# CAN_Mirror.net
KiCad netlist of a schematic drawn in EAGLE
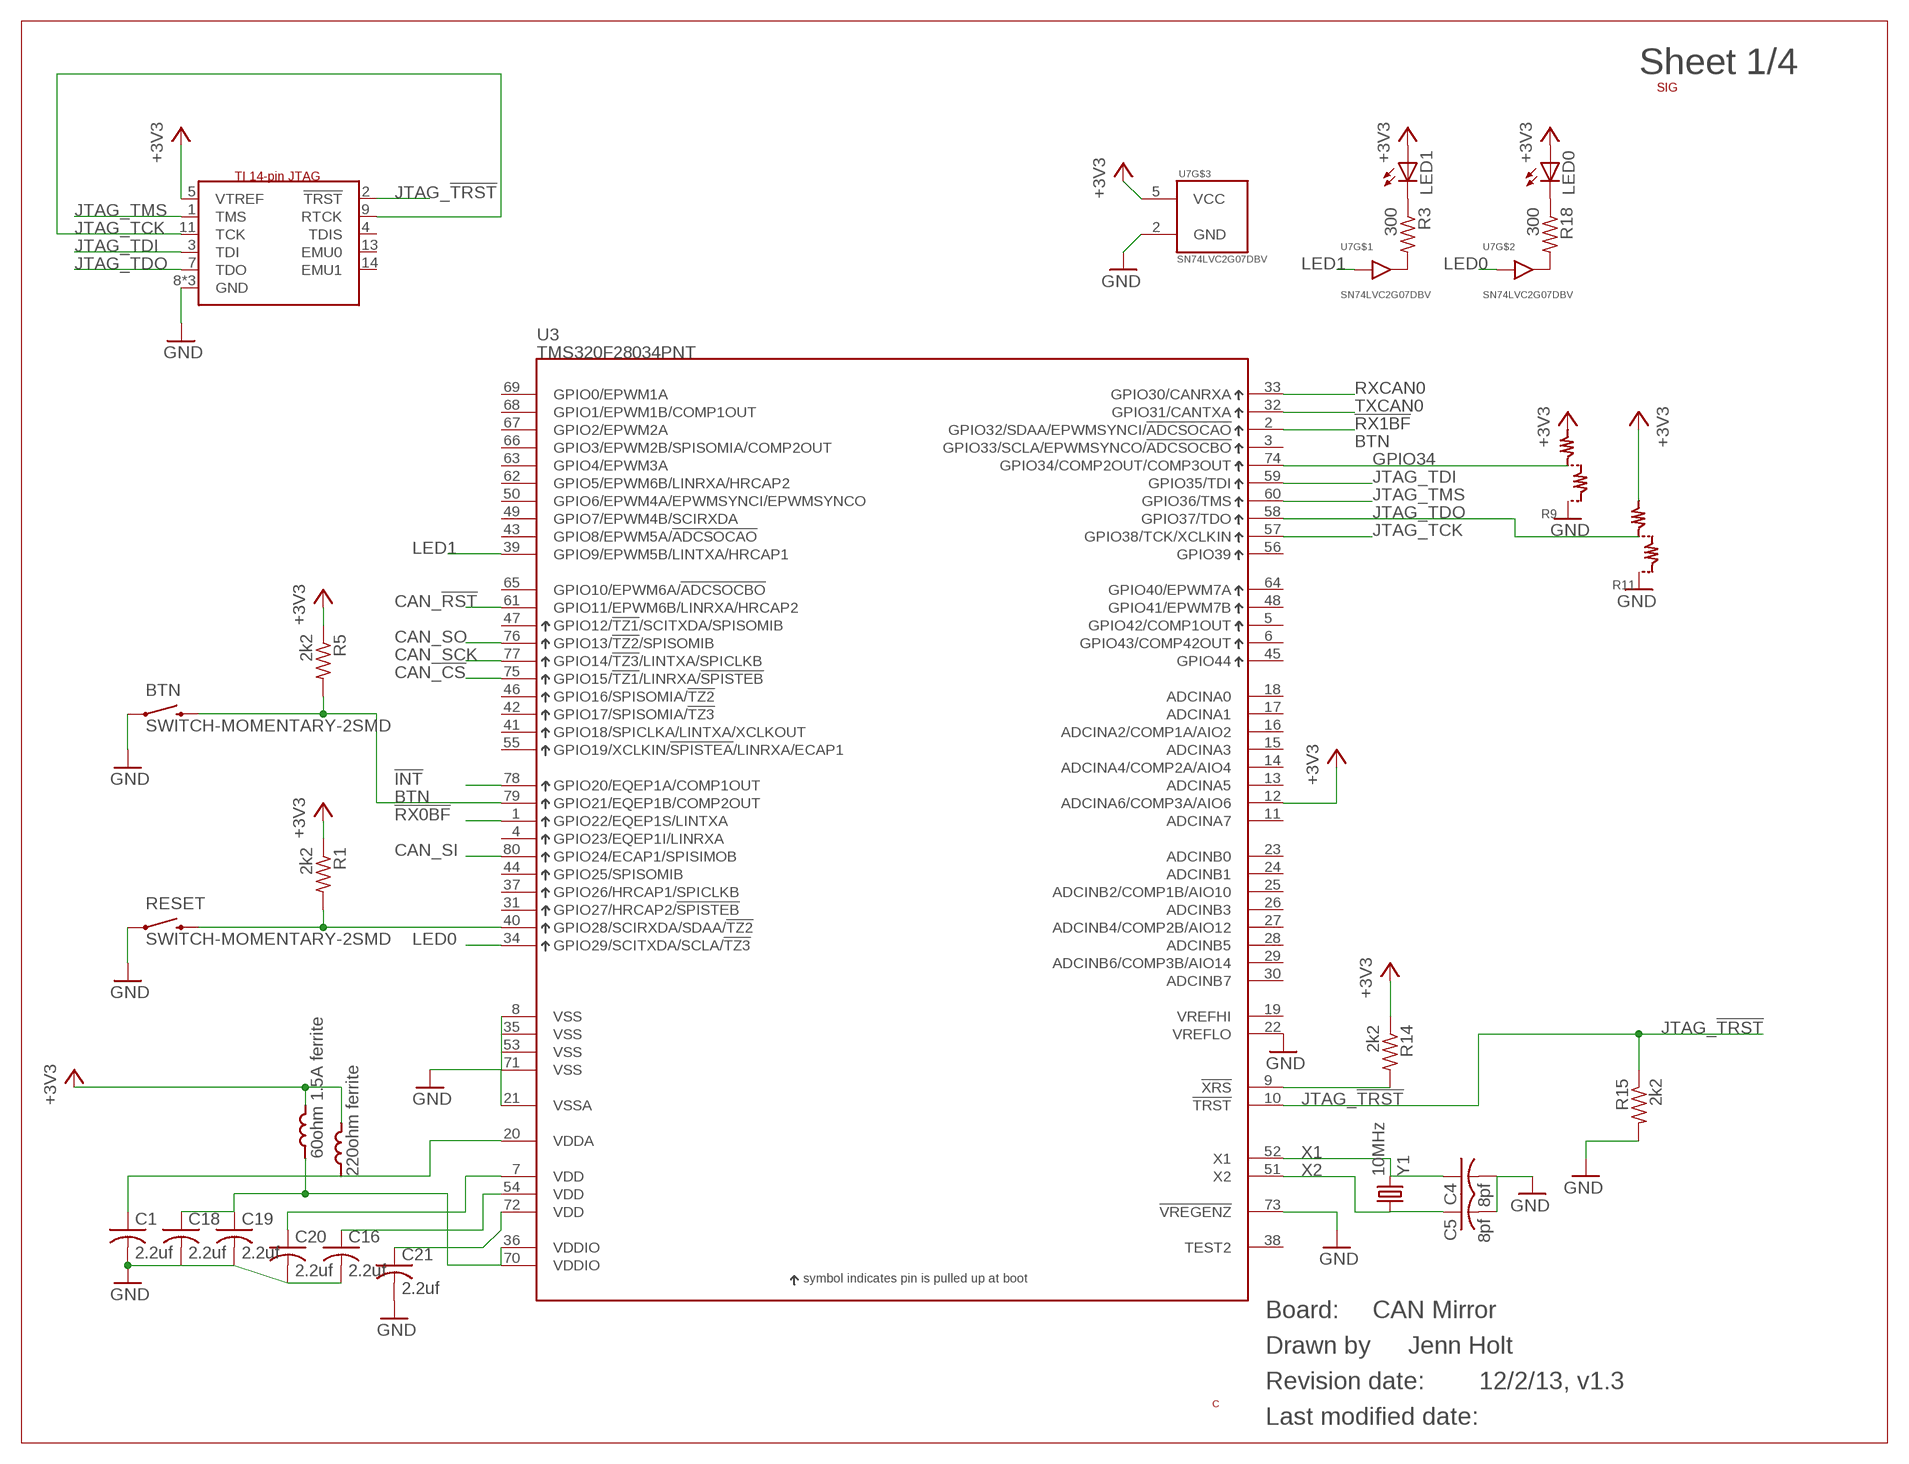
[diagram p0: schematic, sheet 1]
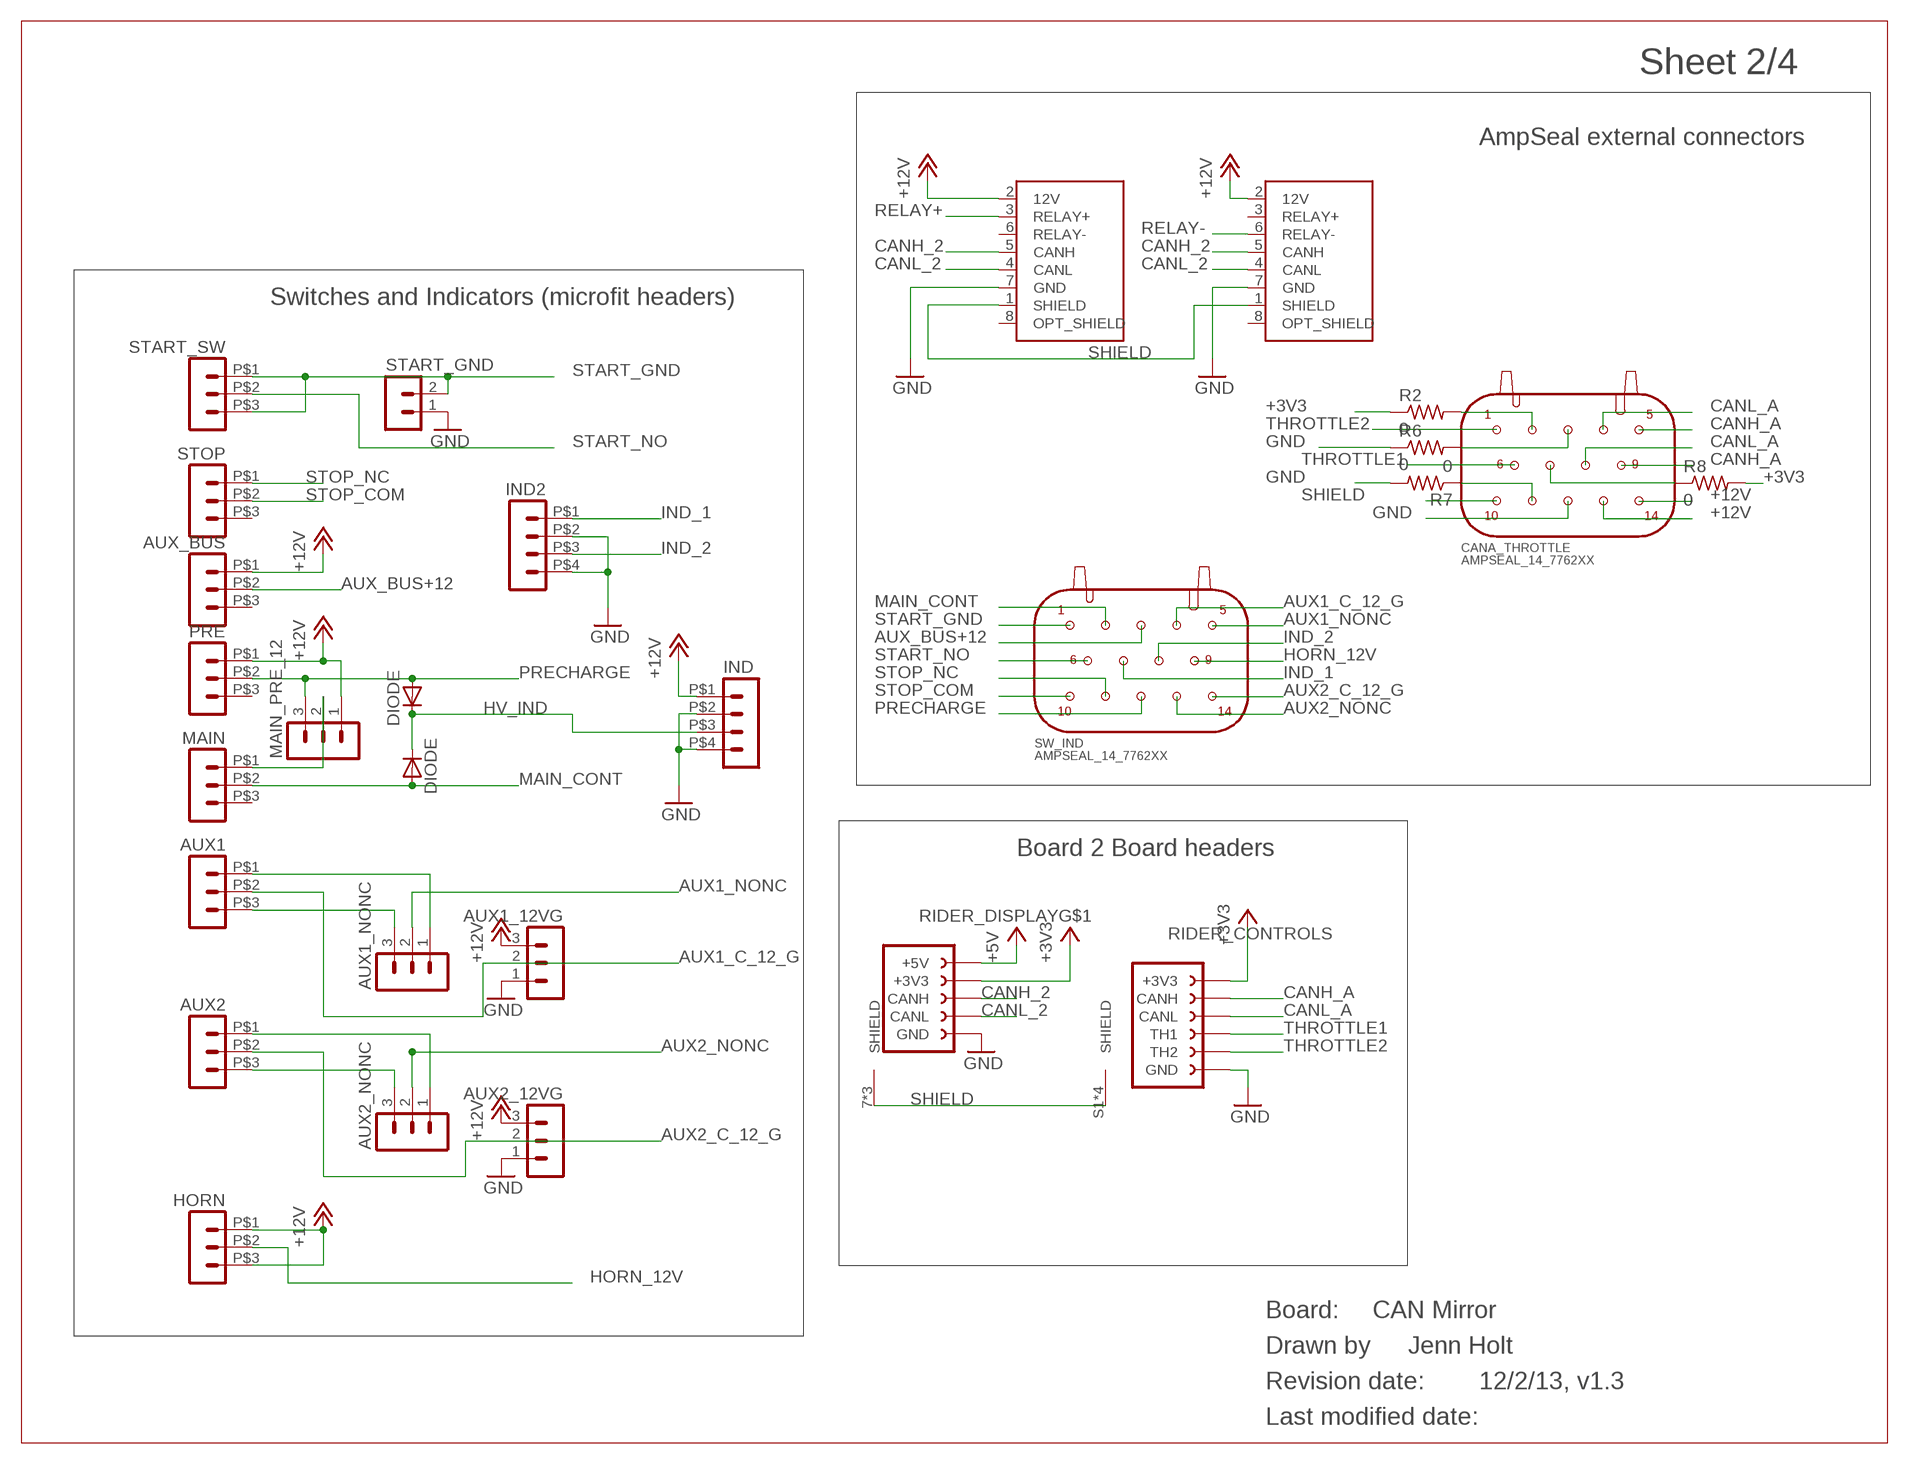
[diagram p1: schematic, sheet 2]
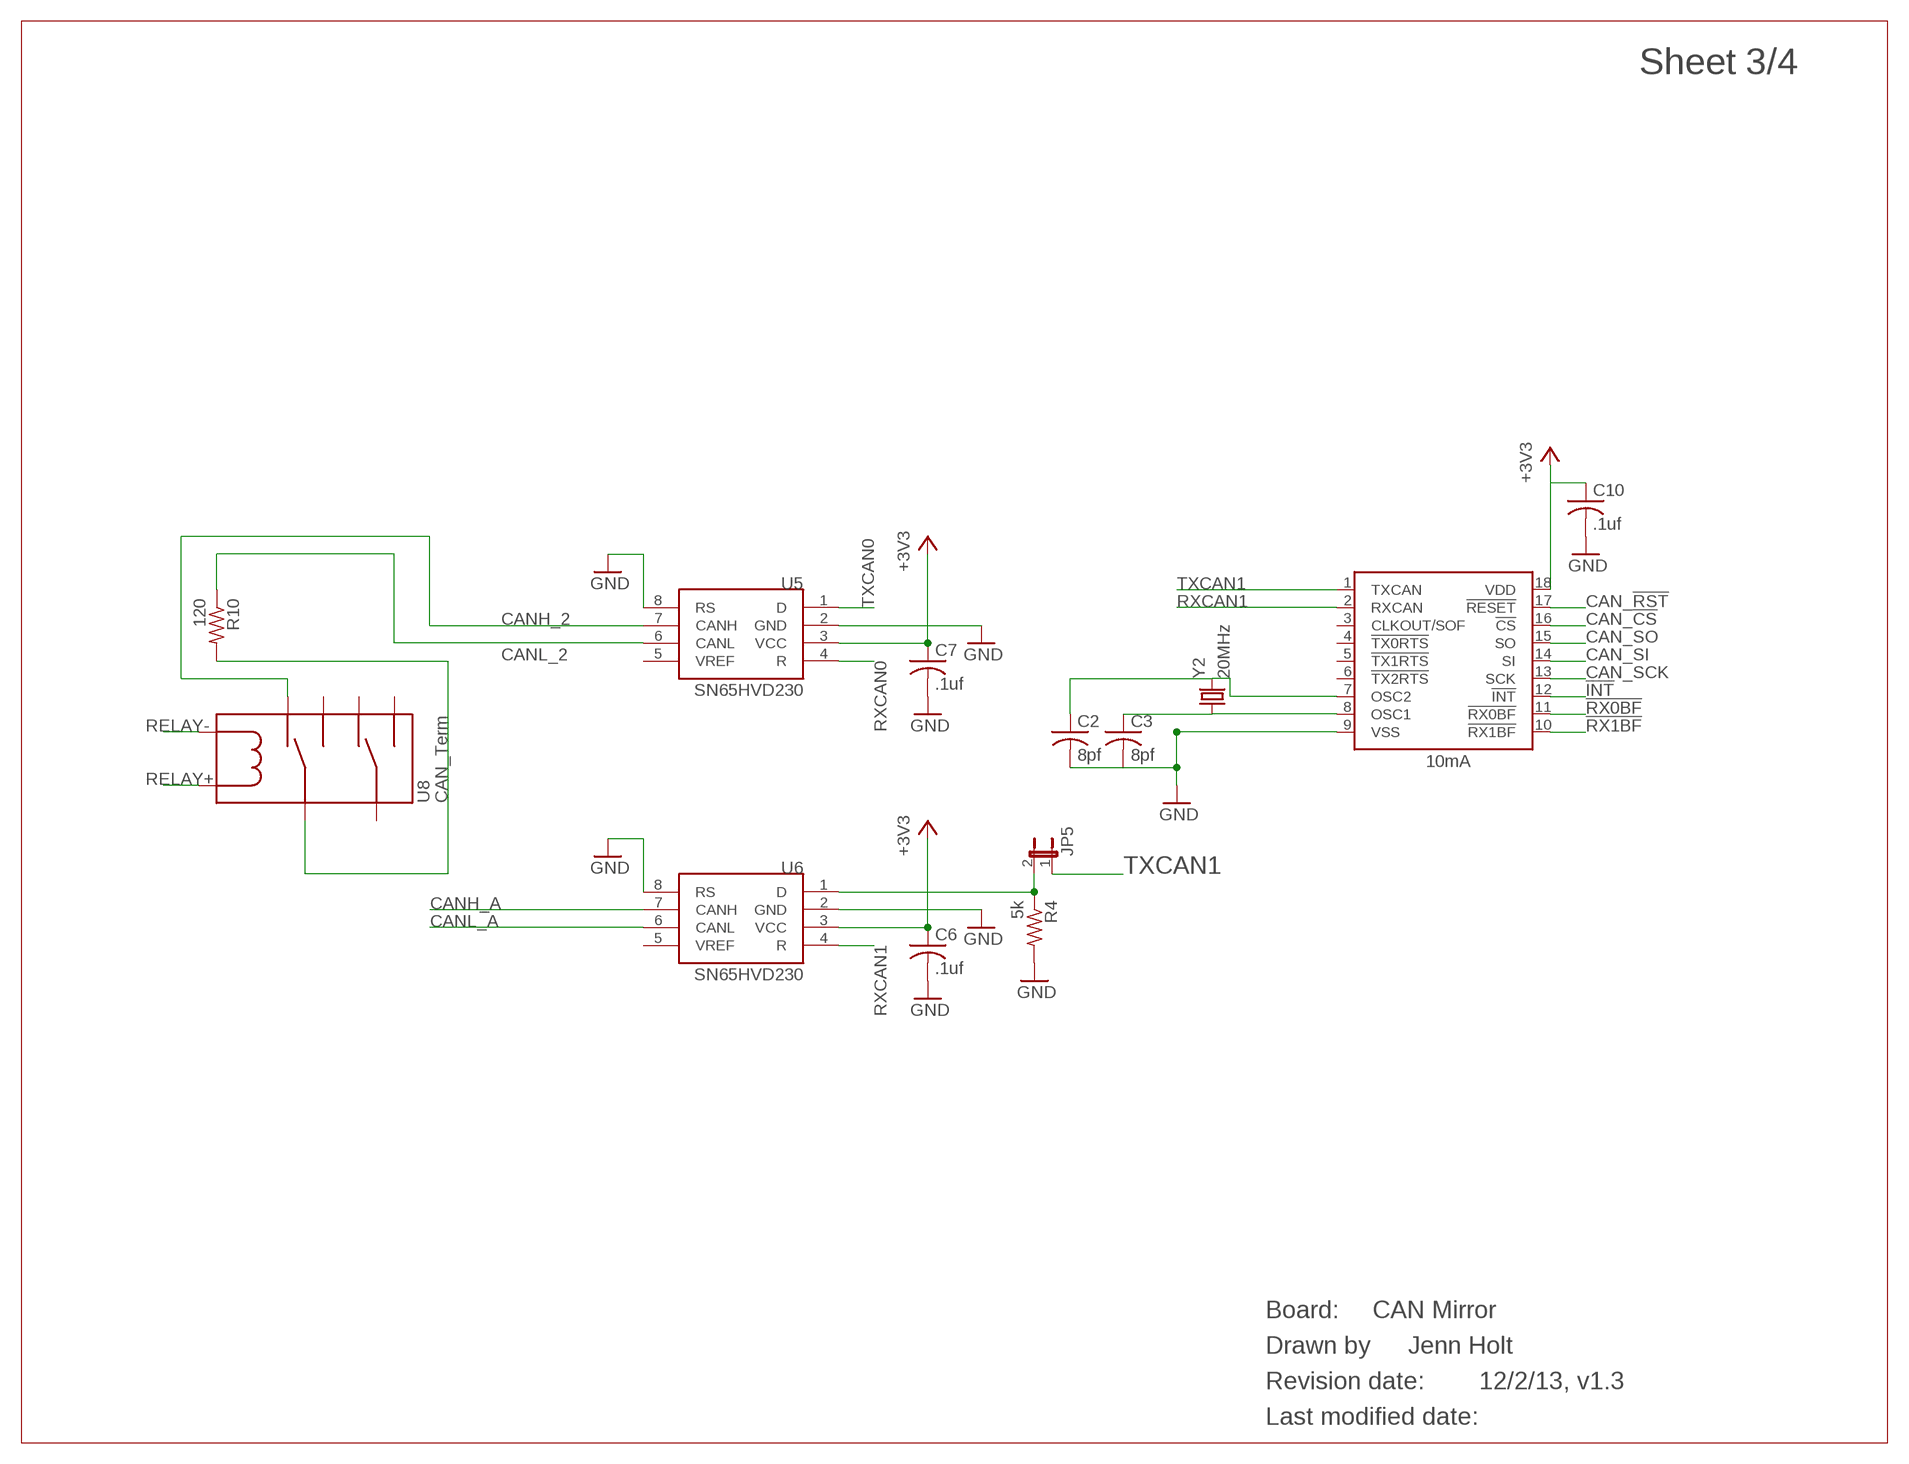
[diagram p2: schematic, sheet 3]
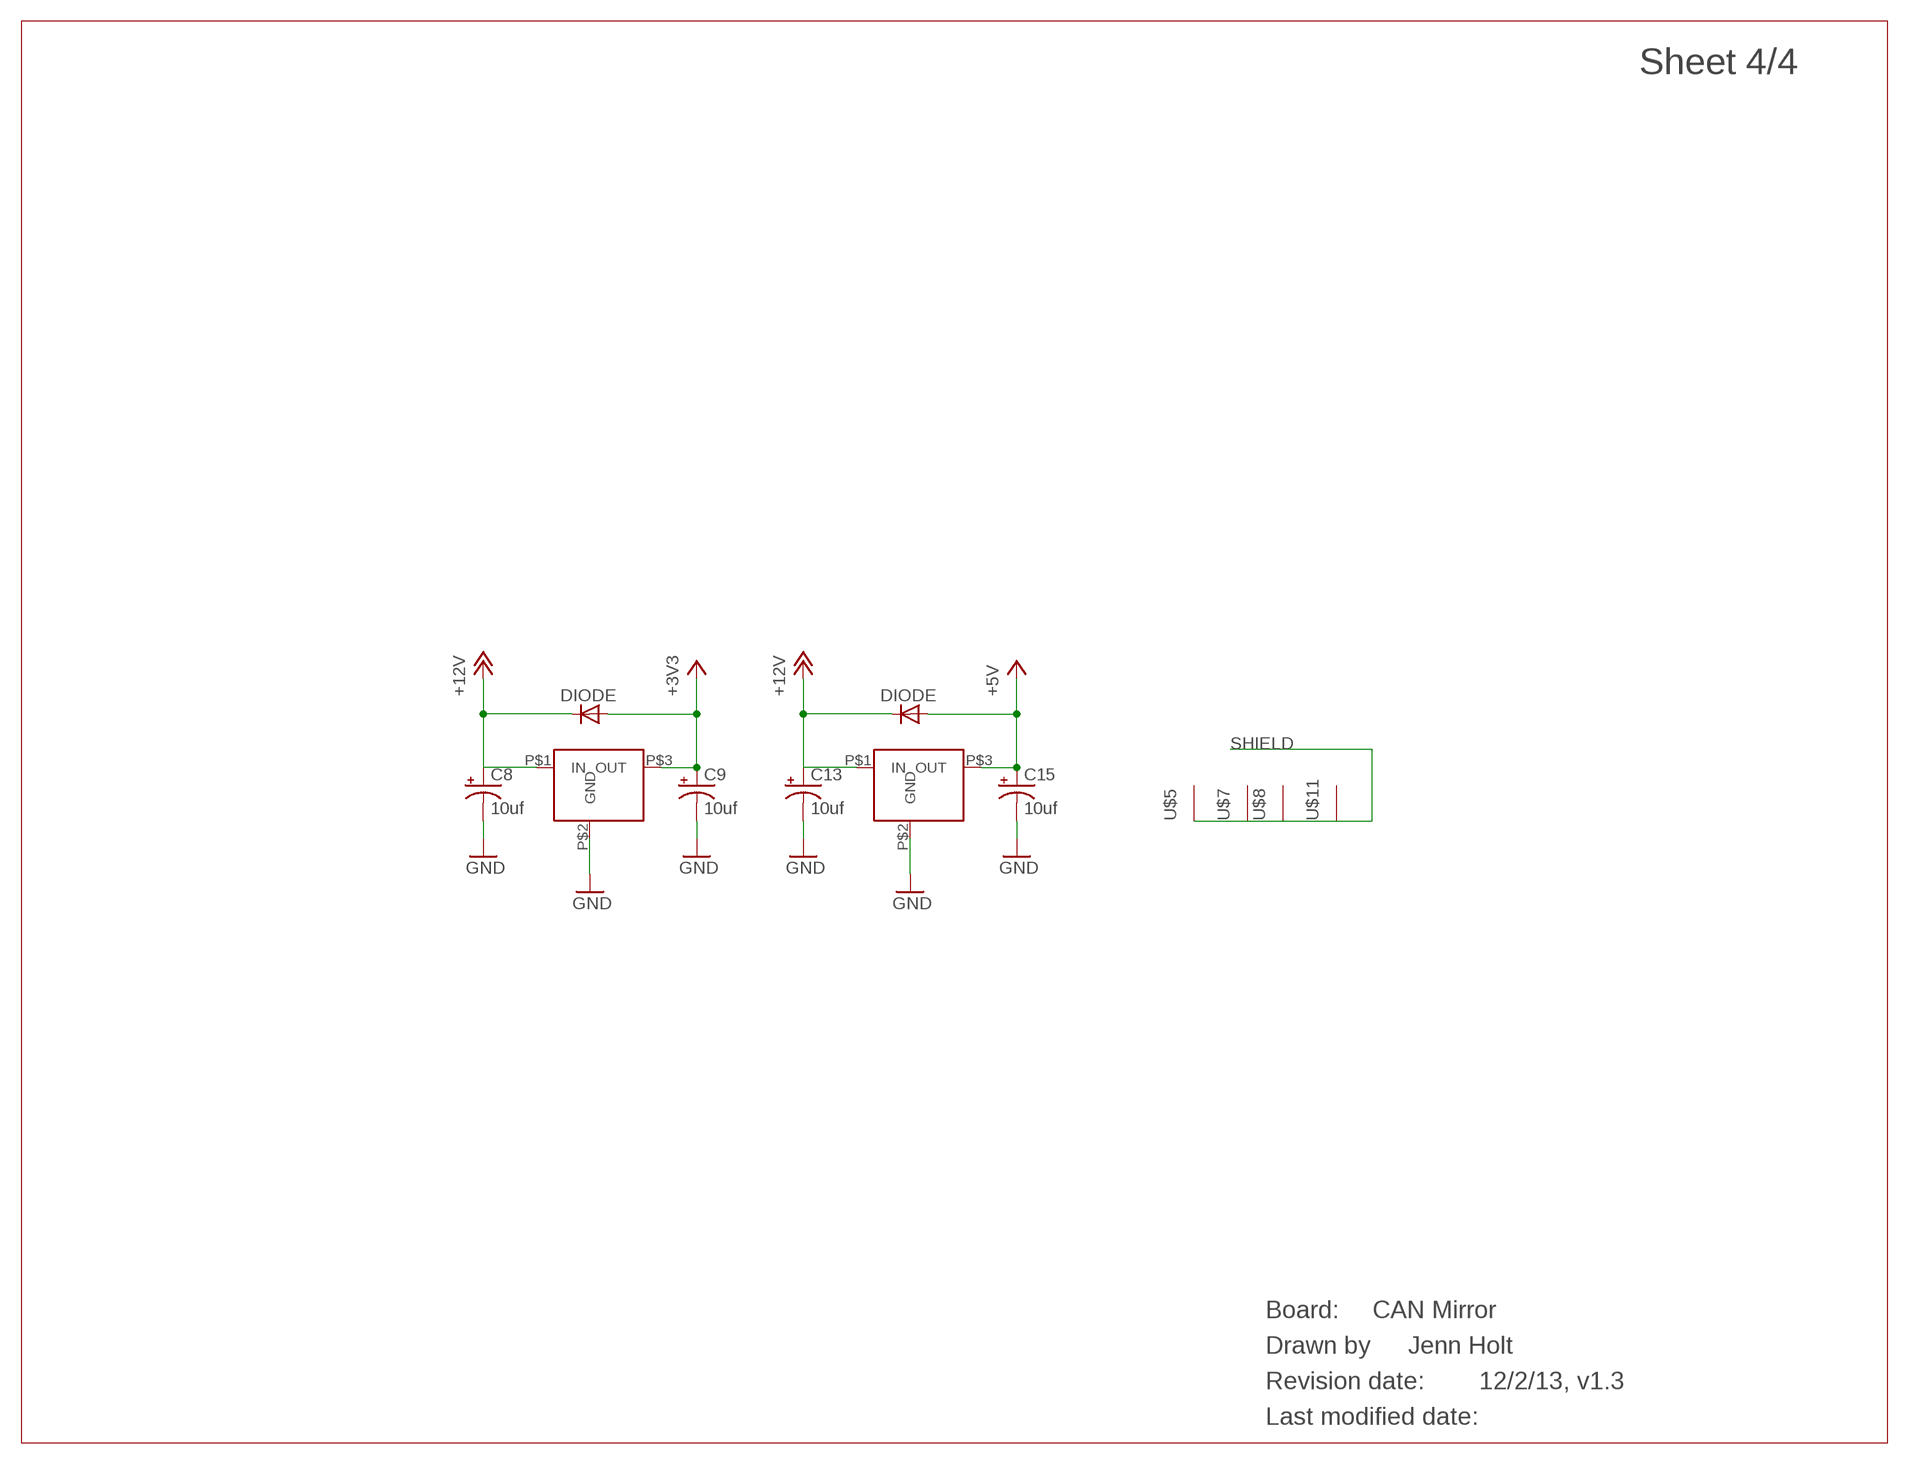
[diagram p3: schematic, sheet 4]

(export (version "E")
  (design (tool "Eeschema 10.0.6"))
  (components
    (comp (ref "C2")
      (value "8pf")
      (footprint "eagle-import:C0603")
      (fields (field (name "PARTNO") "C1608C0G1H080D080AA"))
      (libsource (lib "eagle-import") (part "C-USC0603"))
    )
    (comp (ref "C3")
      (value "8pf")
      (footprint "eagle-import:C0603")
      (fields (field (name "PARTNO") "C1608C0G1H080D080AA"))
      (libsource (lib "eagle-import") (part "C-USC0603"))
    )
    (comp (ref "C6")
      (value ".1uf")
      (footprint "eagle-import:C0603")
      (fields (field (name "PARTNO") "C1608X7R1E104K080AA"))
      (libsource (lib "eagle-import") (part "C-USC0603"))
    )
    (comp (ref "C7")
      (value ".1uf")
      (footprint "eagle-import:C0603")
      (fields (field (name "PARTNO") "C1608X7R1E104K080AA"))
      (libsource (lib "eagle-import") (part "C-USC0603"))
    )
    (comp (ref "C10")
      (value ".1uf")
      (footprint "eagle-import:C0603")
      (fields (field (name "PARTNO") "C1608X7R1E104K080AA"))
      (libsource (lib "eagle-import") (part "C-USC0603"))
    )
    (comp (ref "JP5")
      (value "JUMPER-2SMD-NO")
      (footprint "eagle-import:SJ_2S-NO")
      (libsource (lib "eagle-import") (part "JUMPER-2SMD-NO"))
    )
    (comp (ref "R4")
      (value "5k")
      (footprint "eagle-import:R0603")
      (fields (field (name "PARTNO") "ERJ-3EKF4701V"))
      (libsource (lib "eagle-import") (part "R-US_R0603"))
    )
    (comp (ref "R10")
      (value "120")
      (footprint "eagle-import:R0603")
      (fields (field (name "PARTNO") "RC0805FR-07120RL"))
      (libsource (lib "eagle-import") (part "R-US_R0603"))
    )
    (comp (ref "U$16")
      (value "CURRENT-FRAME-LETTER-LANDSCAPE")
      (footprint "eagle-import:BLANK")
      (libsource (lib "eagle-import") (part "CURRENT-FRAME-LETTER-LANDSCAPE"))
    )
    (comp (ref "U4")
      (value "MCP2515")
      (footprint "eagle-import:SO-18W")
      (fields (field (name "PARTNO") "MCP2515-I/SO"))
      (libsource (lib "eagle-import") (part "MCP2515"))
    )
    (comp (ref "U5")
      (value "SN65HVD230")
      (footprint "eagle-import:SOIC8")
      (fields (field (name "PARTNO") "SN65HVD230D"))
      (libsource (lib "eagle-import") (part "SN65HVD230"))
    )
    (comp (ref "U6")
      (value "SN65HVD230")
      (footprint "eagle-import:SOIC8")
      (fields (field (name "PARTNO") "SN65HVD230D"))
      (libsource (lib "eagle-import") (part "SN65HVD230"))
    )
    (comp (ref "U8")
      (value "CAN_Term")
      (footprint "eagle-import:IM_RELAY")
      (fields (field (name "PARTNO") "IM26GR"))
      (libsource (lib "eagle-import") (part "IM_RELAY"))
    )
    (comp (ref "Y2")
      (value "20MHz")
      (footprint "eagle-import:CRYSTAL-SMD-5X3")
      (fields (field (name "PARTNO") "ECS-200-8-30B-CKM"))
      (libsource (lib "eagle-import") (part "CRYSTAL5X3"))
    )
    (comp (ref "C8")
      (value "10uf")
      (footprint "eagle-import:CT3216")
      (fields (field (name "PARTNO") "T491A106M020AT"))
      (libsource (lib "eagle-import") (part "CPOL-USCT3216"))
    )
    (comp (ref "C9")
      (value "10uf")
      (footprint "eagle-import:CT3216")
      (fields (field (name "PARTNO") "T491A106M020AT"))
      (libsource (lib "eagle-import") (part "CPOL-USCT3216"))
    )
    (comp (ref "C13")
      (value "10uf")
      (footprint "eagle-import:CT3216")
      (fields (field (name "PARTNO") "T491A106M020AT"))
      (libsource (lib "eagle-import") (part "CPOL-USCT3216"))
    )
    (comp (ref "C15")
      (value "10uf")
      (footprint "eagle-import:CT3216")
      (fields (field (name "PARTNO") "T491A106M020AT"))
      (libsource (lib "eagle-import") (part "CPOL-USCT3216"))
    )
    (comp (ref "D3")
      (value "DIODE")
      (footprint "eagle-import:SOD-123")
      (fields (field (name "PARTNO") "MBR0540T1G"))
      (libsource (lib "eagle-import") (part "DIODE"))
    )
    (comp (ref "D4")
      (value "DIODE")
      (footprint "eagle-import:SOD-123")
      (fields (field (name "PARTNO") "MBR0540T1G"))
      (libsource (lib "eagle-import") (part "DIODE"))
    )
    (comp (ref "U$5")
      (value "MOUNT_HOLE")
      (footprint "eagle-import:MOUNT_HOLE_125")
      (libsource (lib "eagle-import") (part "MOUNT_HOLE"))
    )
    (comp (ref "U$7")
      (value "MOUNT_HOLE")
      (footprint "eagle-import:MOUNT_HOLE_125")
      (libsource (lib "eagle-import") (part "MOUNT_HOLE"))
    )
    (comp (ref "U$8")
      (value "MOUNT_HOLE")
      (footprint "eagle-import:MOUNT_HOLE_125")
      (libsource (lib "eagle-import") (part "MOUNT_HOLE"))
    )
    (comp (ref "U$11")
      (value "MOUNT_HOLE")
      (footprint "eagle-import:MOUNT_HOLE_125")
      (libsource (lib "eagle-import") (part "MOUNT_HOLE"))
    )
    (comp (ref "U$17")
      (value "CURRENT-FRAME-LETTER-LANDSCAPE")
      (footprint "eagle-import:BLANK")
      (libsource (lib "eagle-import") (part "CURRENT-FRAME-LETTER-LANDSCAPE"))
    )
    (comp (ref "U1")
      (value "RECOM_DCDC3v3")
      (footprint "eagle-import:INNOLINE-SIP")
      (fields (field (name "PARTNO") "R-78C3.3-1.0"))
      (libsource (lib "eagle-import") (part "RECOM_DCDC"))
    )
    (comp (ref "U2")
      (value "RECOM_DCDC5v")
      (footprint "eagle-import:INNOLINE-SIP")
      (fields (field (name "PARTNO") "R-78C5.0-1.0"))
      (libsource (lib "eagle-import") (part "RECOM_DCDC"))
    )
    (comp (ref "AUX1")
      (value "HEADER_POS3_43650-0321")
      (footprint "eagle-import:43650-0321")
      (fields (field (name "PARTNO") "43650-0321"))
      (libsource (lib "eagle-import") (part "HEADER_POS3_?43650-0321"))
    )
    (comp (ref "AUX1_12VG")
      (value "MA03-1")
      (footprint "eagle-import:MA03-1")
      (fields (field (name "PARTNO") "9-146274-0-20"))
      (libsource (lib "eagle-import") (part "MA03-1"))
    )
    (comp (ref "AUX1_NONC")
      (value "MA03-1")
      (footprint "eagle-import:MA03-1")
      (fields (field (name "PARTNO") "9-146274-0-20"))
      (libsource (lib "eagle-import") (part "MA03-1"))
    )
    (comp (ref "AUX2")
      (value "HEADER_POS3_43650-0321")
      (footprint "eagle-import:43650-0321")
      (fields (field (name "PARTNO") "43650-0321"))
      (libsource (lib "eagle-import") (part "HEADER_POS3_?43650-0321"))
    )
    (comp (ref "AUX2_12VG")
      (value "MA03-1")
      (footprint "eagle-import:MA03-1")
      (fields (field (name "PARTNO") "9-146274-0-20"))
      (libsource (lib "eagle-import") (part "MA03-1"))
    )
    (comp (ref "AUX2_NONC")
      (value "MA03-1")
      (footprint "eagle-import:MA03-1")
      (fields (field (name "PARTNO") "9-146274-0-20"))
      (libsource (lib "eagle-import") (part "MA03-1"))
    )
    (comp (ref "AUX_BUS")
      (value "HEADER_POS3_43650-0321")
      (footprint "eagle-import:43650-0321")
      (fields (field (name "PARTNO") "43650-0321"))
      (libsource (lib "eagle-import") (part "HEADER_POS3_?43650-0321"))
    )
    (comp (ref "CANA_THROTTLE")
      (value "AMPSEAL_14_7762XX")
      (footprint "eagle-import:776262-1_AMPSEAL_14_VERT")
      (fields (field (name "PARTNO") "776262-1"))
      (libsource (lib "eagle-import") (part "AMPSEAL_14_7762XX"))
    )
    (comp (ref "D1")
      (value "DIODE")
      (footprint "eagle-import:SOD-123")
      (fields (field (name "PARTNO") "MBR0540T1G"))
      (libsource (lib "eagle-import") (part "DIODE"))
    )
    (comp (ref "D5")
      (value "DIODE")
      (footprint "eagle-import:SOD-123")
      (fields (field (name "PARTNO") "MBR0540T1G"))
      (libsource (lib "eagle-import") (part "DIODE"))
    )
    (comp (ref "HORN")
      (value "HEADER_POS3_43650-0321")
      (footprint "eagle-import:43650-0321")
      (fields (field (name "PARTNO") "43650-0321"))
      (libsource (lib "eagle-import") (part "HEADER_POS3_?43650-0321"))
    )
    (comp (ref "IND")
      (value "HEADER_POS4_43045-0415")
      (footprint "eagle-import:43045-0415")
      (fields (field (name "PARTNO") "43045-0415"))
      (libsource (lib "eagle-import") (part "HEADER_POS4_?43045-0415"))
    )
    (comp (ref "IND2")
      (value "HEADER_POS4_43045-0415")
      (footprint "eagle-import:43045-0415")
      (fields (field (name "PARTNO") "43045-0415"))
      (libsource (lib "eagle-import") (part "HEADER_POS4_?43045-0415"))
    )
    (comp (ref "MAIN")
      (value "HEADER_POS3_43650-0321")
      (footprint "eagle-import:43650-0321")
      (fields (field (name "PARTNO") "43650-0321"))
      (libsource (lib "eagle-import") (part "HEADER_POS3_?43650-0321"))
    )
    (comp (ref "MAIN_PRE_12")
      (value "MA03-1")
      (footprint "eagle-import:MA03-1")
      (fields
        (field (name "OC_FARNELL") "unknown")
        (field (name "OC_NEWARK") "unknown")
        (field (name "PARTNO") "9-146274-0-20")
      )
      (libsource (lib "eagle-import") (part "MA03-1"))
    )
    (comp (ref "PRE")
      (value "HEADER_POS3_43650-0321")
      (footprint "eagle-import:43650-0321")
      (fields (field (name "PARTNO") "43650-0321"))
      (libsource (lib "eagle-import") (part "HEADER_POS3_?43650-0321"))
    )
    (comp (ref "R2")
      (value "0")
      (footprint "eagle-import:R0603")
      (fields (field (name "PARTNO") "CRCW06030000Z0EA"))
      (libsource (lib "eagle-import") (part "R-US_R0603"))
    )
    (comp (ref "R6")
      (value "0")
      (footprint "eagle-import:R0603")
      (fields (field (name "PARTNO") "CRCW06030000Z0EA"))
      (libsource (lib "eagle-import") (part "R-US_R0603"))
    )
    (comp (ref "R7")
      (value "0")
      (footprint "eagle-import:R0603")
      (fields (field (name "PARTNO") "CRCW06030000Z0EA"))
      (libsource (lib "eagle-import") (part "R-US_R0603"))
    )
    (comp (ref "R8")
      (value "0")
      (footprint "eagle-import:R0603")
      (fields (field (name "PARTNO") "CRCW06030000Z0EA"))
      (libsource (lib "eagle-import") (part "R-US_R0603"))
    )
    (comp (ref "RIDER_CONTROLS")
      (value "RIDER_CONTROLS")
      (footprint "eagle-import:RIDER_CONTROLS")
      (fields (field (name "PARTNO") "534237-4"))
      (libsource (lib "eagle-import") (part "RIDER_CONTROLS"))
    )
    (comp (ref "RIDER_DISPLAY")
      (value "RIDER_DISPLAY")
      (footprint "eagle-import:DISPLAY_BOARD")
      (fields (field (name "PARTNO") "534237-4"))
      (libsource (lib "eagle-import") (part "RIDER_DISPLAY"))
    )
    (comp (ref "START_GND")
      (value "MA02-1")
      (footprint "eagle-import:MA02-1")
      (fields (field (name "PARTNO") "9-146274-0-20"))
      (libsource (lib "eagle-import") (part "MA02-1"))
    )
    (comp (ref "START_SW")
      (value "HEADER_POS3_43650-0321")
      (footprint "eagle-import:43650-0321")
      (fields (field (name "PARTNO") "43650-0321"))
      (libsource (lib "eagle-import") (part "HEADER_POS3_?43650-0321"))
    )
    (comp (ref "STOP")
      (value "HEADER_POS3_43650-0321")
      (footprint "eagle-import:43650-0321")
      (fields (field (name "PARTNO") "43650-0321"))
      (libsource (lib "eagle-import") (part "HEADER_POS3_?43650-0321"))
    )
    (comp (ref "SW_IND")
      (value "AMPSEAL_14_7762XX")
      (footprint "eagle-import:776262-1_AMPSEAL_14_VERT")
      (fields (field (name "PARTNO") "776262-1"))
      (libsource (lib "eagle-import") (part "AMPSEAL_14_7762XX"))
    )
    (comp (ref "U$12")
      (value "CURRENT-FRAME-LETTER-LANDSCAPE")
      (footprint "eagle-import:BLANK")
      (libsource (lib "eagle-import") (part "CURRENT-FRAME-LETTER-LANDSCAPE"))
    )
    (comp (ref "U$13")
      (value "CANBUS2VERT")
      (footprint "eagle-import:776276-1_AMPSEAL_8_VERT")
      (fields (field (name "PARTNO") "1-776276-1"))
      (libsource (lib "eagle-import") (part "CANBUS2VERT"))
    )
    (comp (ref "U$14")
      (value "CANBUS2VERT")
      (footprint "eagle-import:776276-1_AMPSEAL_8_VERT")
      (fields (field (name "PARTNO") "1-776276-1"))
      (libsource (lib "eagle-import") (part "CANBUS2VERT"))
    )
    (comp (ref "BTN")
      (value "SWITCH-MOMENTARY-2SMD")
      (footprint "eagle-import:TACTILE_SWITCH_SMD")
      (fields (field (name "PARTNO") "RS-187R05A2-DS MT RT"))
      (libsource (lib "eagle-import") (part "SWITCH-MOMENTARY-2SMD"))
    )
    (comp (ref "C1")
      (value "2.2uf")
      (footprint "eagle-import:C0603")
      (fields (field (name "PARTNO") "GRM188R61E225KA12D"))
      (libsource (lib "eagle-import") (part "C-USC0603"))
    )
    (comp (ref "C4")
      (value "8pf")
      (footprint "eagle-import:C0603")
      (fields (field (name "PARTNO") "C1608C0G1H080D080AA"))
      (libsource (lib "eagle-import") (part "C-USC0603"))
    )
    (comp (ref "C5")
      (value "8pf")
      (footprint "eagle-import:C0603")
      (fields (field (name "PARTNO") "C1608C0G1H080D080AA"))
      (libsource (lib "eagle-import") (part "C-USC0603"))
    )
    (comp (ref "C16")
      (value "2.2uf")
      (footprint "eagle-import:C0603")
      (fields (field (name "PARTNO") "GRM188R61E225KA12D"))
      (libsource (lib "eagle-import") (part "C-USC0603"))
    )
    (comp (ref "C18")
      (value "2.2uf")
      (footprint "eagle-import:C0603")
      (fields (field (name "PARTNO") "GRM188R61E225KA12D"))
      (libsource (lib "eagle-import") (part "C-USC0603"))
    )
    (comp (ref "C19")
      (value "2.2uf")
      (footprint "eagle-import:C0603")
      (fields (field (name "PARTNO") "GRM188R61E225KA12D"))
      (libsource (lib "eagle-import") (part "C-USC0603"))
    )
    (comp (ref "C20")
      (value "2.2uf")
      (footprint "eagle-import:C0603")
      (fields (field (name "PARTNO") "GRM188R61E225KA12D"))
      (libsource (lib "eagle-import") (part "C-USC0603"))
    )
    (comp (ref "C21")
      (value "2.2uf")
      (footprint "eagle-import:C0603")
      (fields (field (name "PARTNO") "GRM188R61E225KA12D"))
      (libsource (lib "eagle-import") (part "C-USC0603"))
    )
    (comp (ref "L1")
      (value "60ohm 1.5A ferrite")
      (footprint "eagle-import:R0603")
      (fields (field (name "PARTNO") "BKP1608HS600-T"))
      (libsource (lib "eagle-import") (part "INDUCTOR_CERAMIC"))
    )
    (comp (ref "L2")
      (value "220ohm ferrite")
      (footprint "eagle-import:R0603")
      (fields (field (name "PARTNO") "MH1608-221Y"))
      (libsource (lib "eagle-import") (part "INDUCTOR_CERAMIC"))
    )
    (comp (ref "LED0")
      (value "LED0603")
      (footprint "eagle-import:LED-0603")
      (fields (field (name "PARTNO") "HSMH-C190"))
      (libsource (lib "eagle-import") (part "LED0603"))
    )
    (comp (ref "LED1")
      (value "LED0603")
      (footprint "eagle-import:LED-0603")
      (fields (field (name "PARTNO") "HSMH-C190"))
      (libsource (lib "eagle-import") (part "LED0603"))
    )
    (comp (ref "R1")
      (value "2k2")
      (footprint "eagle-import:R0603")
      (fields (field (name "PARTNO") "RC0603FR-102K2L"))
      (libsource (lib "eagle-import") (part "R-US_R0603"))
    )
    (comp (ref "R3")
      (value "300")
      (footprint "eagle-import:R0603")
      (fields (field (name "PARTNO") "ERJ-3GEYJ301V"))
      (libsource (lib "eagle-import") (part "R-US_R0603"))
    )
    (comp (ref "R5")
      (value "2k2")
      (footprint "eagle-import:R0603")
      (fields (field (name "PARTNO") "RC0603FR-102K2L"))
      (libsource (lib "eagle-import") (part "R-US_R0603"))
    )
    (comp (ref "R9")
      (value "0402-JUMPER-3WAY-0603")
      (footprint "eagle-import:0603-JUMPER-3WAY")
      (libsource (lib "eagle-import") (part "0402-JUMPER-3WAY-0603"))
    )
    (comp (ref "R11")
      (value "0402-JUMPER-3WAY-0603")
      (footprint "eagle-import:0603-JUMPER-3WAY")
      (libsource (lib "eagle-import") (part "0402-JUMPER-3WAY-0603"))
    )
    (comp (ref "R14")
      (value "2k2")
      (footprint "eagle-import:R0603")
      (fields (field (name "PARTNO") "RC0603FR-102K2L"))
      (libsource (lib "eagle-import") (part "R-US_R0603"))
    )
    (comp (ref "R15")
      (value "2k2")
      (footprint "eagle-import:R0603")
      (fields (field (name "PARTNO") "RC0603FR-102K2L"))
      (libsource (lib "eagle-import") (part "R-US_R0603"))
    )
    (comp (ref "R18")
      (value "300")
      (footprint "eagle-import:R0603")
      (fields (field (name "PARTNO") "ERJ-3GEYJ301V"))
      (libsource (lib "eagle-import") (part "R-US_R0603"))
    )
    (comp (ref "RESET")
      (value "SWITCH-MOMENTARY-2SMD")
      (footprint "eagle-import:TACTILE_SWITCH_SMD")
      (fields (field (name "PARTNO") "RS-187R05A2-DS MT RT"))
      (libsource (lib "eagle-import") (part "SWITCH-MOMENTARY-2SMD"))
    )
    (comp (ref "U$1")
      (value "CURRENT-LOGO-0.5\"")
      (footprint "eagle-import:CURRENT-0.5_")
      (libsource (lib "eagle-import") (part "CURRENT-LOGO-0.5{dblquote}"))
    )
    (comp (ref "U$6")
      (value "TI_JTAG14")
      (footprint "eagle-import:PAK100_2500-14")
      (fields (field (name "PARTNO") "67996-114HLF"))
      (libsource (lib "eagle-import") (part "TI_JTAG14"))
    )
    (comp (ref "U$9")
      (value "CURRENT-FRAME-LETTER-LANDSCAPE")
      (footprint "eagle-import:BLANK")
      (libsource (lib "eagle-import") (part "CURRENT-FRAME-LETTER-LANDSCAPE"))
    )
    (comp (ref "U$20")
      (value "SIG")
      (footprint "eagle-import:SIG")
      (libsource (lib "eagle-import") (part "SIG"))
    )
    (comp (ref "U3")
      (value "TMS320F28034PNT")
      (footprint "eagle-import:PQFP-80_(S-PQFP-G80)")
      (fields (field (name "PARTNO") "TMS320F28035PNT"))
      (libsource (lib "eagle-import") (part "TMS320F28034PNT"))
    )
    (comp (ref "U7")
      (value "SN74LVC2G07DBV")
      (footprint "eagle-import:SOT-6_DDC")
      (fields (field (name "PARTNO") "SN74LVC2G07DBVR"))
      (libsource (lib "eagle-import") (part "SN74LVC2G07DBV"))
    )
    (comp (ref "Y1")
      (value "10MHz")
      (footprint "eagle-import:CRYSTAL-SMD-5X3")
      (fields (field (name "PARTNO") "ECS-100-8-30B-CKM"))
      (libsource (lib "eagle-import") (part "CRYSTAL5X3"))
    )
  )
  (nets
    (net (code "1") (name "+3V3") (class "Default")
      (node (ref "C10") (pin "1") (pinfunction "1_1") (pintype "passive"))
      (node (ref "C6") (pin "1") (pinfunction "1_1") (pintype "passive"))
      (node (ref "C7") (pin "1") (pinfunction "1_1") (pintype "passive"))
      (node (ref "C9") (pin "+") (pinfunction "+_+") (pintype "passive"))
      (node (ref "D4") (pin "A") (pinfunction "A_A") (pintype "passive"))
      (node (ref "L1") (pin "2") (pinfunction "P$2_2") (pintype "passive"))
      (node (ref "L2") (pin "2") (pinfunction "P$2_2") (pintype "passive"))
      (node (ref "LED0") (pin "A") (pinfunction "A_A") (pintype "passive"))
      (node (ref "LED1") (pin "A") (pinfunction "A_A") (pintype "passive"))
      (node (ref "R1") (pin "1") (pinfunction "1_1") (pintype "passive"))
      (node (ref "R11") (pin "B") (pinfunction "B_B") (pintype "passive"))
      (node (ref "R14") (pin "1") (pinfunction "1_1") (pintype "passive"))
      (node (ref "R2") (pin "1") (pinfunction "1_1") (pintype "passive"))
      (node (ref "R5") (pin "1") (pinfunction "1_1") (pintype "passive"))
      (node (ref "R8") (pin "2") (pinfunction "2_2") (pintype "passive"))
      (node (ref "R9") (pin "B") (pinfunction "B_B") (pintype "passive"))
      (node (ref "RIDER_CONTROLS") (pin "6") (pinfunction "+3V3_6") (pintype "passive"))
      (node (ref "RIDER_DISPLAY") (pin "2") (pinfunction "+3V3_2") (pintype "passive"))
      (node (ref "U$6") (pin "5") (pinfunction "VTREF_5") (pintype "bidirectional"))
      (node (ref "U1") (pin "P$3") (pinfunction "OUT_P$3") (pintype "bidirectional"))
      (node (ref "U3") (pin "12") (pinfunction "ADCINA6/COMP3A/AIO6_12") (pintype "bidirectional"))
      (node (ref "U4") (pin "18") (pinfunction "VDD_18") (pintype "bidirectional"))
      (node (ref "U5") (pin "3") (pinfunction "VCC_3") (pintype "bidirectional"))
      (node (ref "U6") (pin "3") (pinfunction "VCC_3") (pintype "bidirectional"))
      (node (ref "U7") (pin "5") (pinfunction "VCC_5") (pintype "power_in"))
    )
    (net (code "2") (name "+5V") (class "Default")
      (node (ref "C15") (pin "+") (pinfunction "+_+") (pintype "passive"))
      (node (ref "D3") (pin "A") (pinfunction "A_A") (pintype "passive"))
      (node (ref "RIDER_DISPLAY") (pin "1") (pinfunction "+5V_1") (pintype "passive"))
      (node (ref "U2") (pin "P$3") (pinfunction "OUT_P$3") (pintype "bidirectional"))
    )
    (net (code "3") (name "+12V") (class "Default")
      (node (ref "AUX1_12VG") (pin "3") (pinfunction "3_3") (pintype "passive"))
      (node (ref "AUX2_12VG") (pin "3") (pinfunction "3_3") (pintype "passive"))
      (node (ref "AUX_BUS") (pin "P$1") (pinfunction "1_P$1") (pintype "passive"))
      (node (ref "C13") (pin "+") (pinfunction "+_+") (pintype "passive"))
      (node (ref "C8") (pin "+") (pinfunction "+_+") (pintype "passive"))
      (node (ref "CANA_THROTTLE") (pin "13") (pinfunction "13_13") (pintype "passive"))
      (node (ref "CANA_THROTTLE") (pin "14") (pinfunction "14_14") (pintype "passive"))
      (node (ref "D3") (pin "C") (pinfunction "C_C") (pintype "passive"))
      (node (ref "D4") (pin "C") (pinfunction "C_C") (pintype "passive"))
      (node (ref "HORN") (pin "P$1") (pinfunction "1_P$1") (pintype "passive"))
      (node (ref "HORN") (pin "P$3") (pinfunction "3_P$3") (pintype "passive"))
      (node (ref "IND") (pin "P$1") (pinfunction "1_P$1") (pintype "passive"))
      (node (ref "MAIN_PRE_12") (pin "1") (pinfunction "1_1") (pintype "passive"))
      (node (ref "PRE") (pin "P$1") (pinfunction "1_P$1") (pintype "passive"))
      (node (ref "U$13") (pin "2") (pinfunction "12V_2") (pintype "bidirectional"))
      (node (ref "U$14") (pin "2") (pinfunction "12V_2") (pintype "bidirectional"))
      (node (ref "U1") (pin "P$1") (pinfunction "IN_P$1") (pintype "bidirectional"))
      (node (ref "U2") (pin "P$1") (pinfunction "IN_P$1") (pintype "bidirectional"))
    )
    (net (code "4") (name "AUX1_C_12_G") (class "Default")
      (node (ref "AUX1") (pin "P$2") (pinfunction "2_P$2") (pintype "passive"))
      (node (ref "AUX1_12VG") (pin "2") (pinfunction "2_2") (pintype "passive"))
      (node (ref "SW_IND") (pin "4") (pinfunction "4_4") (pintype "passive"))
    )
    (net (code "5") (name "AUX1_NONC") (class "Default")
      (node (ref "AUX1_NONC") (pin "2") (pinfunction "2_2") (pintype "passive"))
      (node (ref "SW_IND") (pin "5") (pinfunction "5_5") (pintype "passive"))
    )
    (net (code "6") (name "AUX2_C_12_G") (class "Default")
      (node (ref "AUX2") (pin "P$2") (pinfunction "2_P$2") (pintype "passive"))
      (node (ref "AUX2_12VG") (pin "2") (pinfunction "2_2") (pintype "passive"))
      (node (ref "SW_IND") (pin "14") (pinfunction "14_14") (pintype "passive"))
    )
    (net (code "7") (name "AUX2_NONC") (class "Default")
      (node (ref "AUX2_NONC") (pin "2") (pinfunction "2_2") (pintype "passive"))
      (node (ref "SW_IND") (pin "13") (pinfunction "13_13") (pintype "passive"))
    )
    (net (code "8") (name "AUX_BUS+12") (class "Default")
      (node (ref "AUX_BUS") (pin "P$2") (pinfunction "2_P$2") (pintype "passive"))
      (node (ref "SW_IND") (pin "3") (pinfunction "3_3") (pintype "passive"))
    )
    (net (code "9") (name "BTN") (class "Default")
      (node (ref "BTN") (pin "3") (pinfunction "2_3") (pintype "passive"))
      (node (ref "R5") (pin "2") (pinfunction "2_2") (pintype "passive"))
      (node (ref "U3") (pin "79") (pinfunction "GPIO21/EQEP1B/COMP2OUT_79") (pintype "bidirectional"))
    )
    (net (code "10") (name "CANH_2") (class "Default")
      (node (ref "RIDER_DISPLAY") (pin "4") (pinfunction "CANH_4") (pintype "passive"))
      (node (ref "U$13") (pin "5") (pinfunction "CANH_5") (pintype "bidirectional"))
      (node (ref "U$14") (pin "5") (pinfunction "CANH_5") (pintype "bidirectional"))
      (node (ref "U5") (pin "7") (pinfunction "CANH_7") (pintype "bidirectional"))
      (node (ref "U8") (pin "2") (pinfunction "NC1_2") (pintype "passive"))
    )
    (net (code "11") (name "CANH_A") (class "Default")
      (node (ref "CANA_THROTTLE") (pin "5") (pinfunction "5_5") (pintype "passive"))
      (node (ref "CANA_THROTTLE") (pin "9") (pinfunction "9_9") (pintype "passive"))
      (node (ref "RIDER_CONTROLS") (pin "5") (pinfunction "CANH_5") (pintype "passive"))
      (node (ref "U6") (pin "7") (pinfunction "CANH_7") (pintype "bidirectional"))
    )
    (net (code "12") (name "CANL_2") (class "Default")
      (node (ref "R10") (pin "1") (pinfunction "1_1") (pintype "passive"))
      (node (ref "RIDER_DISPLAY") (pin "3") (pinfunction "CANL_3") (pintype "passive"))
      (node (ref "U$13") (pin "4") (pinfunction "CANL_4") (pintype "bidirectional"))
      (node (ref "U$14") (pin "4") (pinfunction "CANL_4") (pintype "bidirectional"))
      (node (ref "U5") (pin "6") (pinfunction "CANL_6") (pintype "bidirectional"))
    )
    (net (code "13") (name "CANL_A") (class "Default")
      (node (ref "CANA_THROTTLE") (pin "4") (pinfunction "4_4") (pintype "passive"))
      (node (ref "CANA_THROTTLE") (pin "8") (pinfunction "8_8") (pintype "passive"))
      (node (ref "RIDER_CONTROLS") (pin "4") (pinfunction "CANL_4") (pintype "passive"))
      (node (ref "U6") (pin "6") (pinfunction "CANL_6") (pintype "bidirectional"))
    )
    (net (code "14") (name "CAN_SCK") (class "Default")
      (node (ref "U3") (pin "77") (pinfunction "GPIO14/~{TZ3}/LINTXA/SPICLKB_77") (pintype "bidirectional"))
      (node (ref "U4") (pin "13") (pinfunction "SCK_13") (pintype "bidirectional"))
    )
    (net (code "15") (name "CAN_SI") (class "Default")
      (node (ref "U3") (pin "80") (pinfunction "GPIO24/ECAP1/SPISIMOB_80") (pintype "bidirectional"))
      (node (ref "U4") (pin "14") (pinfunction "SI_14") (pintype "bidirectional"))
    )
    (net (code "16") (name "CAN_SO") (class "Default")
      (node (ref "U3") (pin "76") (pinfunction "GPIO13/~{TZ2}/SPISOMIB_76") (pintype "bidirectional"))
      (node (ref "U4") (pin "15") (pinfunction "SO_15") (pintype "bidirectional"))
    )
    (net (code "17") (name "CAN_~{CS}") (class "Default")
      (node (ref "U3") (pin "75") (pinfunction "GPIO15/~{TZ1}/LINRXA/~{SPISTEB}_75") (pintype "bidirectional"))
      (node (ref "U4") (pin "16") (pinfunction "~{CS}_16") (pintype "bidirectional"))
    )
    (net (code "18") (name "CAN_~{RST}") (class "Default")
      (node (ref "U3") (pin "61") (pinfunction "GPIO11/EPWM6B/LINRXA/HRCAP2_61") (pintype "bidirectional"))
      (node (ref "U4") (pin "17") (pinfunction "~{RESET}_17") (pintype "bidirectional"))
    )
    (net (code "19") (name "GND") (class "Default")
      (node (ref "AUX1_12VG") (pin "1") (pinfunction "1_1") (pintype "passive"))
      (node (ref "AUX2_12VG") (pin "1") (pinfunction "1_1") (pintype "passive"))
      (node (ref "BTN") (pin "1") (pinfunction "1_1") (pintype "passive"))
      (node (ref "C1") (pin "2") (pinfunction "2_2") (pintype "passive"))
      (node (ref "C10") (pin "2") (pinfunction "2_2") (pintype "passive"))
      (node (ref "C13") (pin "-") (pinfunction "-_-") (pintype "passive"))
      (node (ref "C15") (pin "-") (pinfunction "-_-") (pintype "passive"))
      (node (ref "C16") (pin "2") (pinfunction "2_2") (pintype "passive"))
      (node (ref "C18") (pin "2") (pinfunction "2_2") (pintype "passive"))
      (node (ref "C19") (pin "2") (pinfunction "2_2") (pintype "passive"))
      (node (ref "C2") (pin "2") (pinfunction "2_2") (pintype "passive"))
      (node (ref "C20") (pin "2") (pinfunction "2_2") (pintype "passive"))
      (node (ref "C21") (pin "2") (pinfunction "2_2") (pintype "passive"))
      (node (ref "C3") (pin "2") (pinfunction "2_2") (pintype "passive"))
      (node (ref "C4") (pin "2") (pinfunction "2_2") (pintype "passive"))
      (node (ref "C5") (pin "2") (pinfunction "2_2") (pintype "passive"))
      (node (ref "C6") (pin "2") (pinfunction "2_2") (pintype "passive"))
      (node (ref "C7") (pin "2") (pinfunction "2_2") (pintype "passive"))
      (node (ref "C8") (pin "-") (pinfunction "-_-") (pintype "passive"))
      (node (ref "C9") (pin "-") (pinfunction "-_-") (pintype "passive"))
      (node (ref "CANA_THROTTLE") (pin "12") (pinfunction "12_12") (pintype "passive"))
      (node (ref "IND") (pin "P$2") (pinfunction "2_P$2") (pintype "passive"))
      (node (ref "IND") (pin "P$4") (pinfunction "4_P$4") (pintype "passive"))
      (node (ref "IND2") (pin "P$2") (pinfunction "2_P$2") (pintype "passive"))
      (node (ref "IND2") (pin "P$4") (pinfunction "4_P$4") (pintype "passive"))
      (node (ref "R11") (pin "C") (pinfunction "C_C") (pintype "passive"))
      (node (ref "R15") (pin "2") (pinfunction "2_2") (pintype "passive"))
      (node (ref "R4") (pin "2") (pinfunction "2_2") (pintype "passive"))
      (node (ref "R6") (pin "1") (pinfunction "1_1") (pintype "passive"))
      (node (ref "R7") (pin "2") (pinfunction "2_2") (pintype "passive"))
      (node (ref "R9") (pin "C") (pinfunction "C_C") (pintype "passive"))
      (node (ref "RESET") (pin "1") (pinfunction "1_1") (pintype "passive"))
      (node (ref "RIDER_CONTROLS") (pin "1") (pinfunction "GND_1") (pintype "passive"))
      (node (ref "RIDER_DISPLAY") (pin "5") (pinfunction "GND_5") (pintype "passive"))
      (node (ref "RIDER_DISPLAY") (pin "6") (pinfunction "GND_6") (pintype "passive"))
      (node (ref "START_GND") (pin "1") (pinfunction "2_1") (pintype "passive"))
      (node (ref "U$13") (pin "7") (pinfunction "GND_7") (pintype "bidirectional"))
      (node (ref "U$14") (pin "7") (pinfunction "GND_7") (pintype "bidirectional"))
      (node (ref "U$6") (pin "10") (pinfunction "GND_10") (pintype "bidirectional"))
      (node (ref "U$6") (pin "12") (pinfunction "GND_12") (pintype "bidirectional"))
      (node (ref "U$6") (pin "8") (pinfunction "GND_8") (pintype "bidirectional"))
      (node (ref "U1") (pin "P$2") (pinfunction "GND_P$2") (pintype "bidirectional"))
      (node (ref "U2") (pin "P$2") (pinfunction "GND_P$2") (pintype "bidirectional"))
      (node (ref "U3") (pin "21") (pinfunction "VSSA_21") (pintype "power_in"))
      (node (ref "U3") (pin "22") (pinfunction "VREFLO_22") (pintype "input"))
      (node (ref "U3") (pin "35") (pinfunction "VSS_35") (pintype "power_in"))
      (node (ref "U3") (pin "53") (pinfunction "VSS_53") (pintype "power_in"))
      (node (ref "U3") (pin "71") (pinfunction "VSS_71") (pintype "power_in"))
      (node (ref "U3") (pin "73") (pinfunction "~{VREGENZ}_73") (pintype "bidirectional"))
      (node (ref "U3") (pin "8") (pinfunction "VSS_8") (pintype "power_in"))
      (node (ref "U4") (pin "9") (pinfunction "VSS_9") (pintype "bidirectional"))
      (node (ref "U5") (pin "2") (pinfunction "GND_2") (pintype "bidirectional"))
      (node (ref "U5") (pin "8") (pinfunction "RS_8") (pintype "bidirectional"))
      (node (ref "U6") (pin "2") (pinfunction "GND_2") (pintype "bidirectional"))
      (node (ref "U6") (pin "8") (pinfunction "RS_8") (pintype "bidirectional"))
      (node (ref "U7") (pin "2") (pinfunction "GND_2") (pintype "power_in"))
    )
    (net (code "20") (name "GPIO34") (class "Default")
      (node (ref "R9") (pin "A") (pinfunction "A_A") (pintype "passive"))
      (node (ref "U3") (pin "74") (pinfunction "GPIO34/COMP2OUT/COMP3OUT_74") (pintype "bidirectional"))
    )
    (net (code "21") (name "HORN_12V") (class "Default")
      (node (ref "HORN") (pin "P$2") (pinfunction "2_P$2") (pintype "passive"))
      (node (ref "SW_IND") (pin "9") (pinfunction "9_9") (pintype "passive"))
    )
    (net (code "22") (name "HV_IND") (class "Default")
      (node (ref "D1") (pin "C") (pinfunction "C_C") (pintype "passive"))
      (node (ref "D5") (pin "C") (pinfunction "C_C") (pintype "passive"))
      (node (ref "IND") (pin "P$3") (pinfunction "3_P$3") (pintype "passive"))
    )
    (net (code "23") (name "IND_1") (class "Default")
      (node (ref "IND2") (pin "P$1") (pinfunction "1_P$1") (pintype "passive"))
      (node (ref "SW_IND") (pin "7") (pinfunction "7_7") (pintype "passive"))
    )
    (net (code "24") (name "IND_2") (class "Default")
      (node (ref "IND2") (pin "P$3") (pinfunction "3_P$3") (pintype "passive"))
      (node (ref "SW_IND") (pin "8") (pinfunction "8_8") (pintype "passive"))
    )
    (net (code "25") (name "JTAG_TCK") (class "Default")
      (node (ref "U$6") (pin "11") (pinfunction "TCK_11") (pintype "bidirectional"))
      (node (ref "U$6") (pin "9") (pinfunction "RTCK_9") (pintype "bidirectional"))
      (node (ref "U3") (pin "57") (pinfunction "GPIO38/TCK/XCLKIN_57") (pintype "bidirectional"))
    )
    (net (code "26") (name "JTAG_TDI") (class "Default")
      (node (ref "U$6") (pin "3") (pinfunction "TDI_3") (pintype "bidirectional"))
      (node (ref "U3") (pin "59") (pinfunction "GPIO35/TDI_59") (pintype "bidirectional"))
    )
    (net (code "27") (name "JTAG_TDO") (class "Default")
      (node (ref "R11") (pin "A") (pinfunction "A_A") (pintype "passive"))
      (node (ref "U$6") (pin "7") (pinfunction "TDO_7") (pintype "bidirectional"))
      (node (ref "U3") (pin "58") (pinfunction "GPIO37/TDO_58") (pintype "bidirectional"))
    )
    (net (code "28") (name "JTAG_TMS") (class "Default")
      (node (ref "U$6") (pin "1") (pinfunction "TMS_1") (pintype "bidirectional"))
      (node (ref "U3") (pin "60") (pinfunction "GPIO36/TMS_60") (pintype "bidirectional"))
    )
    (net (code "29") (name "JTAG_~{TRST}") (class "Default")
      (node (ref "R15") (pin "1") (pinfunction "1_1") (pintype "passive"))
      (node (ref "U$6") (pin "2") (pinfunction "~{TRST}_2") (pintype "bidirectional"))
      (node (ref "U3") (pin "10") (pinfunction "~{TRST}_10") (pintype "bidirectional"))
    )
    (net (code "30") (name "LED0") (class "Default")
      (node (ref "U3") (pin "34") (pinfunction "GPIO29/SCITXDA/SCLA/~{TZ3}_34") (pintype "bidirectional"))
      (node (ref "U7") (pin "3") (pinfunction "A_3") (pintype "input"))
    )
    (net (code "31") (name "LED1") (class "Default")
      (node (ref "U3") (pin "39") (pinfunction "GPIO9/EPWM5B/LINTXA/HRCAP1_39") (pintype "bidirectional"))
      (node (ref "U7") (pin "1") (pinfunction "A_1") (pintype "input"))
    )
    (net (code "32") (name "MAIN_CONT") (class "Default")
      (node (ref "D5") (pin "A") (pinfunction "A_A") (pintype "passive"))
      (node (ref "MAIN") (pin "P$2") (pinfunction "2_P$2") (pintype "passive"))
      (node (ref "SW_IND") (pin "2") (pinfunction "2_2") (pintype "passive"))
    )
    (net (code "33") (name "Net-(AUX1-1)") (class "Default")
      (node (ref "AUX1") (pin "P$1") (pinfunction "1_P$1") (pintype "passive"))
      (node (ref "AUX1_NONC") (pin "1") (pinfunction "1_1") (pintype "passive"))
    )
    (net (code "34") (name "Net-(AUX1-3)") (class "Default")
      (node (ref "AUX1") (pin "P$3") (pinfunction "3_P$3") (pintype "passive"))
      (node (ref "AUX1_NONC") (pin "3") (pinfunction "3_3") (pintype "passive"))
    )
    (net (code "35") (name "Net-(AUX2-1)") (class "Default")
      (node (ref "AUX2") (pin "P$1") (pinfunction "1_P$1") (pintype "passive"))
      (node (ref "AUX2_NONC") (pin "1") (pinfunction "1_1") (pintype "passive"))
    )
    (net (code "36") (name "Net-(AUX2-3)") (class "Default")
      (node (ref "AUX2") (pin "P$3") (pinfunction "3_P$3") (pintype "passive"))
      (node (ref "AUX2_NONC") (pin "3") (pinfunction "3_3") (pintype "passive"))
    )
    (net (code "37") (name "Net-(C16-Pad1)") (class "Default")
      (node (ref "C16") (pin "1") (pinfunction "1_1") (pintype "passive"))
      (node (ref "U3") (pin "54") (pinfunction "VDD_54") (pintype "power_in"))
    )
    (net (code "38") (name "Net-(C20-Pad1)") (class "Default")
      (node (ref "C20") (pin "1") (pinfunction "1_1") (pintype "passive"))
      (node (ref "U3") (pin "7") (pinfunction "VDD_7") (pintype "power_in"))
    )
    (net (code "39") (name "Net-(C21-Pad1)") (class "Default")
      (node (ref "C21") (pin "1") (pinfunction "1_1") (pintype "passive"))
      (node (ref "U3") (pin "72") (pinfunction "VDD_72") (pintype "power_in"))
    )
    (net (code "40") (name "Net-(CANA_THROTTLE-Pad2)") (class "Default")
      (node (ref "CANA_THROTTLE") (pin "2") (pinfunction "2_2") (pintype "passive"))
      (node (ref "R2") (pin "2") (pinfunction "2_2") (pintype "passive"))
    )
    (net (code "41") (name "Net-(CANA_THROTTLE-Pad3)") (class "Default")
      (node (ref "CANA_THROTTLE") (pin "3") (pinfunction "3_3") (pintype "passive"))
      (node (ref "R6") (pin "2") (pinfunction "2_2") (pintype "passive"))
    )
    (net (code "42") (name "Net-(CANA_THROTTLE-Pad7)") (class "Default")
      (node (ref "CANA_THROTTLE") (pin "7") (pinfunction "7_7") (pintype "passive"))
      (node (ref "R8") (pin "1") (pinfunction "1_1") (pintype "passive"))
    )
    (net (code "43") (name "Net-(CANA_THROTTLE-Pad11)") (class "Default")
      (node (ref "CANA_THROTTLE") (pin "11") (pinfunction "11_11") (pintype "passive"))
      (node (ref "R7") (pin "1") (pinfunction "1_1") (pintype "passive"))
    )
    (net (code "44") (name "Net-(L1-P$1)") (class "Default")
      (node (ref "C18") (pin "1") (pinfunction "1_1") (pintype "passive"))
      (node (ref "C19") (pin "1") (pinfunction "1_1") (pintype "passive"))
      (node (ref "L1") (pin "1") (pinfunction "P$1_1") (pintype "passive"))
      (node (ref "U3") (pin "36") (pinfunction "VDDIO_36") (pintype "power_in"))
      (node (ref "U3") (pin "70") (pinfunction "VDDIO_70") (pintype "power_in"))
    )
    (net (code "45") (name "Net-(L2-P$1)") (class "Default")
      (node (ref "C1") (pin "1") (pinfunction "1_1") (pintype "passive"))
      (node (ref "L2") (pin "1") (pinfunction "P$1_1") (pintype "passive"))
      (node (ref "U3") (pin "20") (pinfunction "VDDA_20") (pintype "power_in"))
    )
    (net (code "46") (name "Net-(LED0-PadC)") (class "Default")
      (node (ref "LED0") (pin "C") (pinfunction "C_C") (pintype "passive"))
      (node (ref "R18") (pin "1") (pinfunction "1_1") (pintype "passive"))
    )
    (net (code "47") (name "Net-(LED1-PadC)") (class "Default")
      (node (ref "LED1") (pin "C") (pinfunction "C_C") (pintype "passive"))
      (node (ref "R3") (pin "1") (pinfunction "1_1") (pintype "passive"))
    )
    (net (code "48") (name "Net-(MAIN-1)") (class "Default")
      (node (ref "MAIN") (pin "P$1") (pinfunction "1_P$1") (pintype "passive"))
      (node (ref "MAIN_PRE_12") (pin "2") (pinfunction "2_2") (pintype "passive"))
    )
    (net (code "49") (name "Net-(RESET-2)") (class "Default")
      (node (ref "R1") (pin "2") (pinfunction "2_2") (pintype "passive"))
      (node (ref "RESET") (pin "3") (pinfunction "2_3") (pintype "passive"))
      (node (ref "U3") (pin "40") (pinfunction "GPIO28/SCIRXDA/SDAA/~{TZ2}_40") (pintype "bidirectional"))
    )
    (net (code "50") (name "Net-(U3-~{XRS})") (class "Default")
      (node (ref "R14") (pin "2") (pinfunction "2_2") (pintype "passive"))
      (node (ref "U3") (pin "9") (pinfunction "~{XRS}_9") (pintype "bidirectional"))
    )
    (net (code "51") (name "Net-(U4-OSC1)") (class "Default")
      (node (ref "C3") (pin "1") (pinfunction "1_1") (pintype "passive"))
      (node (ref "U4") (pin "8") (pinfunction "OSC1_8") (pintype "bidirectional"))
      (node (ref "Y2") (pin "1") (pinfunction "1_1") (pintype "passive"))
    )
    (net (code "52") (name "Net-(U4-OSC2)") (class "Default")
      (node (ref "C2") (pin "1") (pinfunction "1_1") (pintype "passive"))
      (node (ref "U4") (pin "7") (pinfunction "OSC2_7") (pintype "bidirectional"))
      (node (ref "Y2") (pin "3") (pinfunction "2_3") (pintype "passive"))
    )
    (net (code "53") (name "Net-(U6-D)") (class "Default")
      (node (ref "JP5") (pin "2") (pinfunction "2_2") (pintype "passive"))
      (node (ref "R4") (pin "1") (pinfunction "1_1") (pintype "passive"))
      (node (ref "U6") (pin "1") (pinfunction "D_1") (pintype "bidirectional"))
    )
    (net (code "54") (name "Net-(U7A-Y)") (class "Default")
      (node (ref "R3") (pin "2") (pinfunction "2_2") (pintype "passive"))
      (node (ref "U7") (pin "6") (pinfunction "Y_6") (pintype "output"))
    )
    (net (code "55") (name "Net-(U7B-Y)") (class "Default")
      (node (ref "R18") (pin "2") (pinfunction "2_2") (pintype "passive"))
      (node (ref "U7") (pin "4") (pinfunction "Y_4") (pintype "output"))
    )
    (net (code "56") (name "Net-(U8-COM1)") (class "Default")
      (node (ref "R10") (pin "2") (pinfunction "2_2") (pintype "passive"))
      (node (ref "U8") (pin "3") (pinfunction "COM1_3") (pintype "passive"))
    )
    (net (code "57") (name "PRECHARGE") (class "Default")
      (node (ref "D1") (pin "A") (pinfunction "A_A") (pintype "passive"))
      (node (ref "MAIN_PRE_12") (pin "3") (pinfunction "3_3") (pintype "passive"))
      (node (ref "PRE") (pin "P$2") (pinfunction "2_P$2") (pintype "passive"))
      (node (ref "SW_IND") (pin "12") (pinfunction "12_12") (pintype "passive"))
    )
    (net (code "58") (name "RELAY+") (class "Default")
      (node (ref "U$13") (pin "3") (pinfunction "RELAY+_3") (pintype "bidirectional"))
      (node (ref "U8") (pin "1") (pinfunction "C1_1") (pintype "passive"))
    )
    (net (code "59") (name "RELAY-") (class "Default")
      (node (ref "U$14") (pin "6") (pinfunction "RELAY-_6") (pintype "bidirectional"))
      (node (ref "U8") (pin "8") (pinfunction "C2_8") (pintype "passive"))
    )
    (net (code "60") (name "RXCAN0") (class "Default")
      (node (ref "U3") (pin "33") (pinfunction "GPIO30/CANRXA_33") (pintype "bidirectional"))
      (node (ref "U5") (pin "4") (pinfunction "R_4") (pintype "bidirectional"))
    )
    (net (code "61") (name "RXCAN1") (class "Default")
      (node (ref "U4") (pin "2") (pinfunction "RXCAN_2") (pintype "bidirectional"))
      (node (ref "U6") (pin "4") (pinfunction "R_4") (pintype "bidirectional"))
    )
    (net (code "62") (name "SHIELD") (class "Default")
      (node (ref "CANA_THROTTLE") (pin "10") (pinfunction "10_10") (pintype "passive"))
      (node (ref "RIDER_CONTROLS") (pin "S1") (pinfunction "SHIELD_S1") (pintype "bidirectional"))
      (node (ref "RIDER_CONTROLS") (pin "S2") (pinfunction "SHIELD_S2") (pintype "bidirectional"))
      (node (ref "RIDER_CONTROLS") (pin "S3") (pinfunction "SHIELD_S3") (pintype "bidirectional"))
      (node (ref "RIDER_CONTROLS") (pin "S4") (pinfunction "SHIELD_S4") (pintype "bidirectional"))
      (node (ref "RIDER_DISPLAY") (pin "7") (pinfunction "SHIELD_7") (pintype "bidirectional"))
      (node (ref "RIDER_DISPLAY") (pin "8") (pinfunction "SHIELD_8") (pintype "bidirectional"))
      (node (ref "RIDER_DISPLAY") (pin "9") (pinfunction "SHIELD_9") (pintype "bidirectional"))
      (node (ref "U$11") (pin "P$1") (pinfunction "P$1_P$1") (pintype "passive"))
      (node (ref "U$13") (pin "1") (pinfunction "SHIELD_1") (pintype "bidirectional"))
      (node (ref "U$14") (pin "1") (pinfunction "SHIELD_1") (pintype "bidirectional"))
      (node (ref "U$5") (pin "P$1") (pinfunction "P$1_P$1") (pintype "passive"))
      (node (ref "U$7") (pin "P$1") (pinfunction "P$1_P$1") (pintype "passive"))
      (node (ref "U$8") (pin "P$1") (pinfunction "P$1_P$1") (pintype "passive"))
    )
    (net (code "63") (name "START_GND") (class "Default")
      (node (ref "START_GND") (pin "2") (pinfunction "3_2") (pintype "passive"))
      (node (ref "START_SW") (pin "P$1") (pinfunction "1_P$1") (pintype "passive"))
      (node (ref "START_SW") (pin "P$3") (pinfunction "3_P$3") (pintype "passive"))
      (node (ref "SW_IND") (pin "1") (pinfunction "1_1") (pintype "passive"))
    )
    (net (code "64") (name "START_NO") (class "Default")
      (node (ref "START_SW") (pin "P$2") (pinfunction "2_P$2") (pintype "passive"))
      (node (ref "SW_IND") (pin "6") (pinfunction "6_6") (pintype "passive"))
    )
    (net (code "65") (name "STOP_COM") (class "Default")
      (node (ref "STOP") (pin "P$2") (pinfunction "2_P$2") (pintype "passive"))
      (node (ref "SW_IND") (pin "10") (pinfunction "10_10") (pintype "passive"))
    )
    (net (code "66") (name "STOP_NC") (class "Default")
      (node (ref "STOP") (pin "P$1") (pinfunction "1_P$1") (pintype "passive"))
      (node (ref "SW_IND") (pin "11") (pinfunction "11_11") (pintype "passive"))
    )
    (net (code "67") (name "THROTTLE1") (class "Default")
      (node (ref "CANA_THROTTLE") (pin "6") (pinfunction "6_6") (pintype "passive"))
      (node (ref "RIDER_CONTROLS") (pin "3") (pinfunction "TH1_3") (pintype "passive"))
    )
    (net (code "68") (name "THROTTLE2") (class "Default")
      (node (ref "CANA_THROTTLE") (pin "1") (pinfunction "1_1") (pintype "passive"))
      (node (ref "RIDER_CONTROLS") (pin "2") (pinfunction "TH2_2") (pintype "passive"))
    )
    (net (code "69") (name "TXCAN0") (class "Default")
      (node (ref "U3") (pin "32") (pinfunction "GPIO31/CANTXA_32") (pintype "bidirectional"))
      (node (ref "U5") (pin "1") (pinfunction "D_1") (pintype "bidirectional"))
    )
    (net (code "70") (name "TXCAN1") (class "Default")
      (node (ref "JP5") (pin "1") (pinfunction "1_1") (pintype "passive"))
      (node (ref "U4") (pin "1") (pinfunction "TXCAN_1") (pintype "bidirectional"))
    )
    (net (code "71") (name "X1") (class "Default")
      (node (ref "C4") (pin "1") (pinfunction "1_1") (pintype "passive"))
      (node (ref "U3") (pin "52") (pinfunction "X1_52") (pintype "bidirectional"))
      (node (ref "Y1") (pin "3") (pinfunction "2_3") (pintype "passive"))
    )
    (net (code "72") (name "X2") (class "Default")
      (node (ref "C5") (pin "1") (pinfunction "1_1") (pintype "passive"))
      (node (ref "U3") (pin "51") (pinfunction "X2_51") (pintype "bidirectional"))
      (node (ref "Y1") (pin "1") (pinfunction "1_1") (pintype "passive"))
    )
    (net (code "73") (name "unconnected-(AUX_BUS-3-PadP$3)") (class "Default")
      (node (ref "AUX_BUS") (pin "P$3") (pinfunction "3_P$3") (pintype "passive"))
    )
    (net (code "74") (name "unconnected-(MAIN-3-PadP$3)") (class "Default")
      (node (ref "MAIN") (pin "P$3") (pinfunction "3_P$3") (pintype "passive"))
    )
    (net (code "75") (name "unconnected-(PRE-3-PadP$3)") (class "Default")
      (node (ref "PRE") (pin "P$3") (pinfunction "3_P$3") (pintype "passive"))
    )
    (net (code "76") (name "unconnected-(STOP-3-PadP$3)") (class "Default")
      (node (ref "STOP") (pin "P$3") (pinfunction "3_P$3") (pintype "passive"))
    )
    (net (code "77") (name "unconnected-(U$6-EMU0-Pad13)") (class "Default")
      (node (ref "U$6") (pin "13") (pinfunction "EMU0_13") (pintype "bidirectional"))
    )
    (net (code "78") (name "unconnected-(U$6-EMU1-Pad14)") (class "Default")
      (node (ref "U$6") (pin "14") (pinfunction "EMU1_14") (pintype "bidirectional"))
    )
    (net (code "79") (name "unconnected-(U$6-TDIS-Pad4)") (class "Default")
      (node (ref "U$6") (pin "4") (pinfunction "TDIS_4") (pintype "bidirectional"))
    )
    (net (code "80") (name "unconnected-(U$13-OPT_SHIELD-Pad8)") (class "Default")
      (node (ref "U$13") (pin "8") (pinfunction "OPT_SHIELD_8") (pintype "bidirectional"))
    )
    (net (code "81") (name "unconnected-(U$13-RELAY--Pad6)") (class "Default")
      (node (ref "U$13") (pin "6") (pinfunction "RELAY-_6") (pintype "bidirectional"))
    )
    (net (code "82") (name "unconnected-(U$14-OPT_SHIELD-Pad8)") (class "Default")
      (node (ref "U$14") (pin "8") (pinfunction "OPT_SHIELD_8") (pintype "bidirectional"))
    )
    (net (code "83") (name "unconnected-(U$14-RELAY+-Pad3)") (class "Default")
      (node (ref "U$14") (pin "3") (pinfunction "RELAY+_3") (pintype "bidirectional"))
    )
    (net (code "84") (name "unconnected-(U3-ADCINA0-Pad18)") (class "Default")
      (node (ref "U3") (pin "18") (pinfunction "ADCINA0_18") (pintype "input"))
    )
    (net (code "85") (name "unconnected-(U3-ADCINA1-Pad17)") (class "Default")
      (node (ref "U3") (pin "17") (pinfunction "ADCINA1_17") (pintype "input"))
    )
    (net (code "86") (name "unconnected-(U3-ADCINA2{slash}COMP1A{slash}AIO2-Pad16)") (class "Default")
      (node (ref "U3") (pin "16") (pinfunction "ADCINA2/COMP1A/AIO2_16") (pintype "bidirectional"))
    )
    (net (code "87") (name "unconnected-(U3-ADCINA3-Pad15)") (class "Default")
      (node (ref "U3") (pin "15") (pinfunction "ADCINA3_15") (pintype "input"))
    )
    (net (code "88") (name "unconnected-(U3-ADCINA4{slash}COMP2A{slash}AIO4-Pad14)") (class "Default")
      (node (ref "U3") (pin "14") (pinfunction "ADCINA4/COMP2A/AIO4_14") (pintype "bidirectional"))
    )
    (net (code "89") (name "unconnected-(U3-ADCINA5-Pad13)") (class "Default")
      (node (ref "U3") (pin "13") (pinfunction "ADCINA5_13") (pintype "input"))
    )
    (net (code "90") (name "unconnected-(U3-ADCINA7-Pad11)") (class "Default")
      (node (ref "U3") (pin "11") (pinfunction "ADCINA7_11") (pintype "input"))
    )
    (net (code "91") (name "unconnected-(U3-ADCINB0-Pad23)") (class "Default")
      (node (ref "U3") (pin "23") (pinfunction "ADCINB0_23") (pintype "input"))
    )
    (net (code "92") (name "unconnected-(U3-ADCINB1-Pad24)") (class "Default")
      (node (ref "U3") (pin "24") (pinfunction "ADCINB1_24") (pintype "input"))
    )
    (net (code "93") (name "unconnected-(U3-ADCINB2{slash}COMP1B{slash}AIO10-Pad25)") (class "Default")
      (node (ref "U3") (pin "25") (pinfunction "ADCINB2/COMP1B/AIO10_25") (pintype "input"))
    )
    (net (code "94") (name "unconnected-(U3-ADCINB3-Pad26)") (class "Default")
      (node (ref "U3") (pin "26") (pinfunction "ADCINB3_26") (pintype "input"))
    )
    (net (code "95") (name "unconnected-(U3-ADCINB4{slash}COMP2B{slash}AIO12-Pad27)") (class "Default")
      (node (ref "U3") (pin "27") (pinfunction "ADCINB4/COMP2B/AIO12_27") (pintype "input"))
    )
    (net (code "96") (name "unconnected-(U3-ADCINB5-Pad28)") (class "Default")
      (node (ref "U3") (pin "28") (pinfunction "ADCINB5_28") (pintype "input"))
    )
    (net (code "97") (name "unconnected-(U3-ADCINB6{slash}COMP3B{slash}AIO14-Pad29)") (class "Default")
      (node (ref "U3") (pin "29") (pinfunction "ADCINB6/COMP3B/AIO14_29") (pintype "input"))
    )
    (net (code "98") (name "unconnected-(U3-ADCINB7-Pad30)") (class "Default")
      (node (ref "U3") (pin "30") (pinfunction "ADCINB7_30") (pintype "input"))
    )
    (net (code "99") (name "unconnected-(U3-GPIO0{slash}EPWM1A-Pad69)") (class "Default")
      (node (ref "U3") (pin "69") (pinfunction "GPIO0/EPWM1A_69") (pintype "bidirectional"))
    )
    (net (code "100") (name "unconnected-(U3-GPIO1{slash}EPWM1B{slash}COMP1OUT-Pad68)") (class "Default")
      (node (ref "U3") (pin "68") (pinfunction "GPIO1/EPWM1B/COMP1OUT_68") (pintype "bidirectional"))
    )
    (net (code "101") (name "unconnected-(U3-GPIO2{slash}EPWM2A-Pad67)") (class "Default")
      (node (ref "U3") (pin "67") (pinfunction "GPIO2/EPWM2A_67") (pintype "bidirectional"))
    )
    (net (code "102") (name "unconnected-(U3-GPIO3{slash}EPWM2B{slash}SPISOMIA{slash}COMP2OUT-Pad66)") (class "Default")
      (node (ref "U3") (pin "66") (pinfunction "GPIO3/EPWM2B/SPISOMIA/COMP2OUT_66") (pintype "bidirectional"))
    )
    (net (code "103") (name "unconnected-(U3-GPIO4{slash}EPWM3A-Pad63)") (class "Default")
      (node (ref "U3") (pin "63") (pinfunction "GPIO4/EPWM3A_63") (pintype "bidirectional"))
    )
    (net (code "104") (name "unconnected-(U3-GPIO5{slash}EPWM6B{slash}LINRXA{slash}HRCAP2-Pad62)") (class "Default")
      (node (ref "U3") (pin "62") (pinfunction "GPIO5/EPWM6B/LINRXA/HRCAP2_62") (pintype "bidirectional"))
    )
    (net (code "105") (name "unconnected-(U3-GPIO6{slash}EPWM4A{slash}EPWMSYNCI{slash}EPWMSYNCO-Pad50)") (class "Default")
      (node (ref "U3") (pin "50") (pinfunction "GPIO6/EPWM4A/EPWMSYNCI/EPWMSYNCO_50") (pintype "bidirectional"))
    )
    (net (code "106") (name "unconnected-(U3-GPIO7{slash}EPWM4B{slash}SCIRXDA-Pad49)") (class "Default")
      (node (ref "U3") (pin "49") (pinfunction "GPIO7/EPWM4B/SCIRXDA_49") (pintype "bidirectional"))
    )
    (net (code "107") (name "unconnected-(U3-GPIO8{slash}EPWM5A{slash}~{ADCSOCAO}-Pad43)") (class "Default")
      (node (ref "U3") (pin "43") (pinfunction "GPIO8/EPWM5A/~{ADCSOCAO}_43") (pintype "bidirectional"))
    )
    (net (code "108") (name "unconnected-(U3-GPIO10{slash}EPWM6A{slash}~{ADCSOCBO}-Pad65)") (class "Default")
      (node (ref "U3") (pin "65") (pinfunction "GPIO10/EPWM6A/~{ADCSOCBO}_65") (pintype "bidirectional"))
    )
    (net (code "109") (name "unconnected-(U3-GPIO12{slash}~{TZ1}{slash}SCITXDA{slash}SPISOMIB-Pad47)") (class "Default")
      (node (ref "U3") (pin "47") (pinfunction "GPIO12/~{TZ1}/SCITXDA/SPISOMIB_47") (pintype "bidirectional"))
    )
    (net (code "110") (name "unconnected-(U3-GPIO16{slash}SPISOMIA{slash}~{TZ2}-Pad46)") (class "Default")
      (node (ref "U3") (pin "46") (pinfunction "GPIO16/SPISOMIA/~{TZ2}_46") (pintype "bidirectional"))
    )
    (net (code "111") (name "unconnected-(U3-GPIO17{slash}SPISOMIA{slash}~{TZ3}-Pad42)") (class "Default")
      (node (ref "U3") (pin "42") (pinfunction "GPIO17/SPISOMIA/~{TZ3}_42") (pintype "bidirectional"))
    )
    (net (code "112") (name "unconnected-(U3-GPIO18{slash}SPICLKA{slash}LINTXA{slash}XCLKOUT-Pad41)") (class "Default")
      (node (ref "U3") (pin "41") (pinfunction "GPIO18/SPICLKA/LINTXA/XCLKOUT_41") (pintype "bidirectional"))
    )
    (net (code "113") (name "unconnected-(U3-GPIO19{slash}XCLKIN{slash}~{SPISTEA}{slash}LINRXA{slash}ECAP1-Pad55)") (class "Default")
      (node (ref "U3") (pin "55") (pinfunction "GPIO19/XCLKIN/~{SPISTEA}/LINRXA/ECAP1_55") (pintype "bidirectional"))
    )
    (net (code "114") (name "unconnected-(U3-GPIO23{slash}EQEP1I{slash}LINRXA-Pad4)") (class "Default")
      (node (ref "U3") (pin "4") (pinfunction "GPIO23/EQEP1I/LINRXA_4") (pintype "bidirectional"))
    )
    (net (code "115") (name "unconnected-(U3-GPIO25{slash}SPISOMIB-Pad44)") (class "Default")
      (node (ref "U3") (pin "44") (pinfunction "GPIO25/SPISOMIB_44") (pintype "bidirectional"))
    )
    (net (code "116") (name "unconnected-(U3-GPIO26{slash}HRCAP1{slash}SPICLKB-Pad37)") (class "Default")
      (node (ref "U3") (pin "37") (pinfunction "GPIO26/HRCAP1/SPICLKB_37") (pintype "bidirectional"))
    )
    (net (code "117") (name "unconnected-(U3-GPIO27{slash}HRCAP2{slash}~{SPISTEB}-Pad31)") (class "Default")
      (node (ref "U3") (pin "31") (pinfunction "GPIO27/HRCAP2/~{SPISTEB}_31") (pintype "bidirectional"))
    )
    (net (code "118") (name "unconnected-(U3-GPIO33{slash}SCLA{slash}EPWMSYNCO{slash}~{ADCSOCBO}-Pad3)") (class "Default")
      (node (ref "U3") (pin "3") (pinfunction "GPIO33/SCLA/EPWMSYNCO/~{ADCSOCBO}_3") (pintype "bidirectional"))
    )
    (net (code "119") (name "unconnected-(U3-GPIO39-Pad56)") (class "Default")
      (node (ref "U3") (pin "56") (pinfunction "GPIO39_56") (pintype "bidirectional"))
    )
    (net (code "120") (name "unconnected-(U3-GPIO40{slash}EPWM7A-Pad64)") (class "Default")
      (node (ref "U3") (pin "64") (pinfunction "GPIO40/EPWM7A_64") (pintype "bidirectional"))
    )
    (net (code "121") (name "unconnected-(U3-GPIO41{slash}EPWM7B-Pad48)") (class "Default")
      (node (ref "U3") (pin "48") (pinfunction "GPIO41/EPWM7B_48") (pintype "bidirectional"))
    )
    (net (code "122") (name "unconnected-(U3-GPIO42{slash}COMP1OUT-Pad5)") (class "Default")
      (node (ref "U3") (pin "5") (pinfunction "GPIO42/COMP1OUT_5") (pintype "bidirectional"))
    )
    (net (code "123") (name "unconnected-(U3-GPIO43{slash}COMP42OUT-Pad6)") (class "Default")
      (node (ref "U3") (pin "6") (pinfunction "GPIO43/COMP42OUT_6") (pintype "bidirectional"))
    )
    (net (code "124") (name "unconnected-(U3-GPIO44-Pad45)") (class "Default")
      (node (ref "U3") (pin "45") (pinfunction "GPIO44_45") (pintype "bidirectional"))
    )
    (net (code "125") (name "unconnected-(U3-TEST2-Pad38)") (class "Default")
      (node (ref "U3") (pin "38") (pinfunction "TEST2_38") (pintype "no_connect"))
    )
    (net (code "126") (name "unconnected-(U3-VREFHI-Pad19)") (class "Default")
      (node (ref "U3") (pin "19") (pinfunction "VREFHI_19") (pintype "input"))
    )
    (net (code "127") (name "unconnected-(U4-CLKOUT{slash}SOF-Pad3)") (class "Default")
      (node (ref "U4") (pin "3") (pinfunction "CLKOUT/SOF_3") (pintype "bidirectional"))
    )
    (net (code "128") (name "unconnected-(U4-~{TX0RTS}-Pad4)") (class "Default")
      (node (ref "U4") (pin "4") (pinfunction "~{TX0RTS}_4") (pintype "bidirectional"))
    )
    (net (code "129") (name "unconnected-(U4-~{TX1RTS}-Pad5)") (class "Default")
      (node (ref "U4") (pin "5") (pinfunction "~{TX1RTS}_5") (pintype "bidirectional"))
    )
    (net (code "130") (name "unconnected-(U4-~{TX2RTS}-Pad6)") (class "Default")
      (node (ref "U4") (pin "6") (pinfunction "~{TX2RTS}_6") (pintype "bidirectional"))
    )
    (net (code "131") (name "unconnected-(U5-VREF-Pad5)") (class "Default")
      (node (ref "U5") (pin "5") (pinfunction "VREF_5") (pintype "bidirectional"))
    )
    (net (code "132") (name "unconnected-(U6-VREF-Pad5)") (class "Default")
      (node (ref "U6") (pin "5") (pinfunction "VREF_5") (pintype "bidirectional"))
    )
    (net (code "133") (name "unconnected-(U8-COM2-Pad6)") (class "Default")
      (node (ref "U8") (pin "6") (pinfunction "COM2_6") (pintype "passive"))
    )
    (net (code "134") (name "unconnected-(U8-NC2-Pad7)") (class "Default")
      (node (ref "U8") (pin "7") (pinfunction "NC2_7") (pintype "passive"))
    )
    (net (code "135") (name "unconnected-(U8-NO1-Pad4)") (class "Default")
      (node (ref "U8") (pin "4") (pinfunction "NO1_4") (pintype "passive"))
    )
    (net (code "136") (name "unconnected-(U8-NO2-Pad5)") (class "Default")
      (node (ref "U8") (pin "5") (pinfunction "NO2_5") (pintype "passive"))
    )
    (net (code "137") (name "~{INT}") (class "Default")
      (node (ref "U3") (pin "78") (pinfunction "GPIO20/EQEP1A/COMP1OUT_78") (pintype "bidirectional"))
      (node (ref "U4") (pin "12") (pinfunction "~{INT}_12") (pintype "bidirectional"))
    )
    (net (code "138") (name "~{RX0BF}") (class "Default")
      (node (ref "U3") (pin "1") (pinfunction "GPIO22/EQEP1S/LINTXA_1") (pintype "input"))
      (node (ref "U4") (pin "11") (pinfunction "~{RX0BF}_11") (pintype "bidirectional"))
    )
    (net (code "139") (name "~{RX1BF}") (class "Default")
      (node (ref "U3") (pin "2") (pinfunction "GPIO32/SDAA/EPWMSYNCI/~{ADCSOCAO}_2") (pintype "bidirectional"))
      (node (ref "U4") (pin "10") (pinfunction "~{RX1BF}_10") (pintype "bidirectional"))
    )
  )
)
